# PT08M.net
KiCad netlist of a schematic drawn in EAGLE
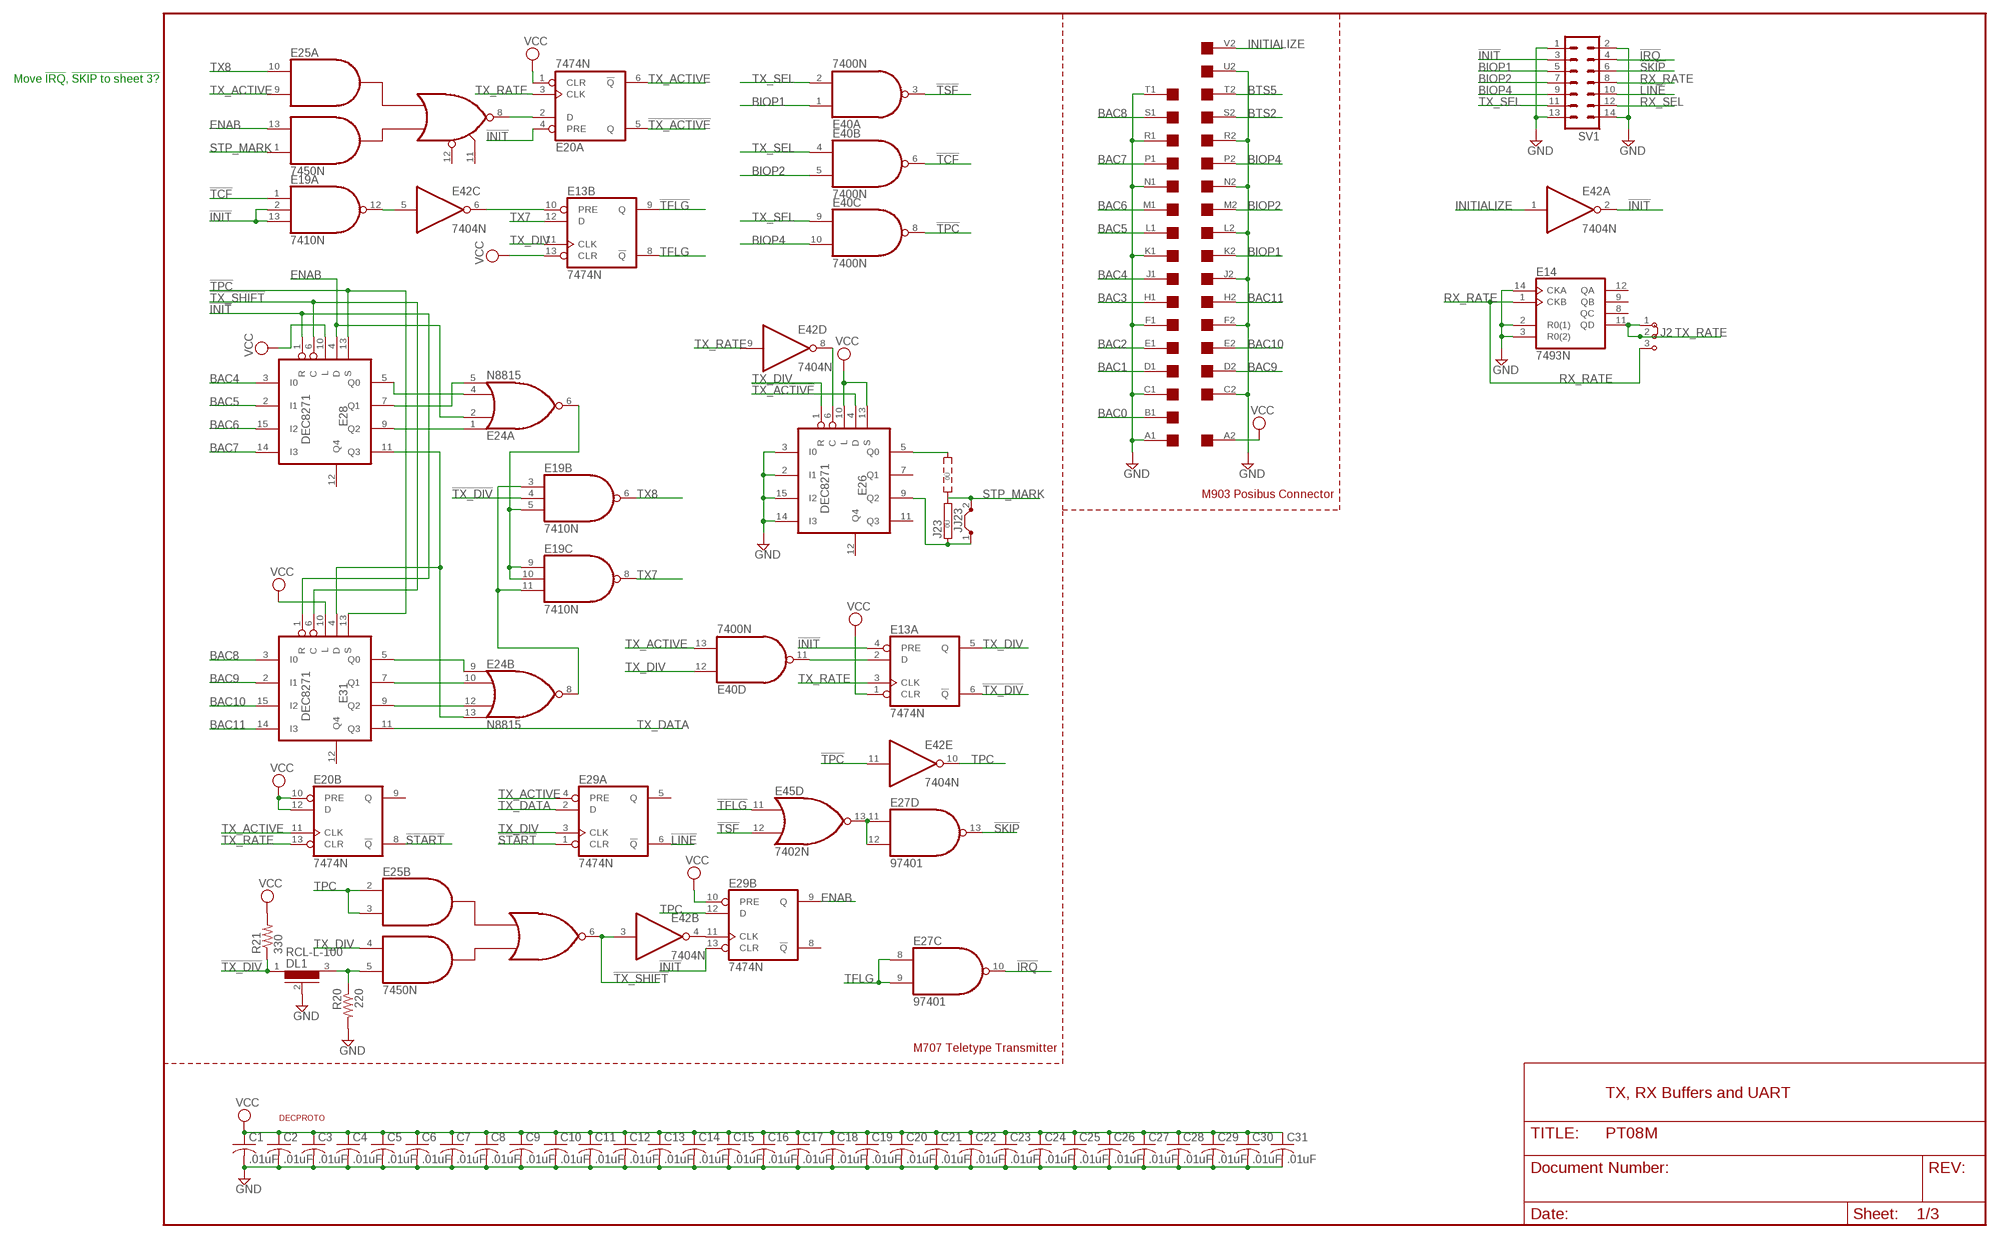
[diagram p0: schematic, sheet 1]
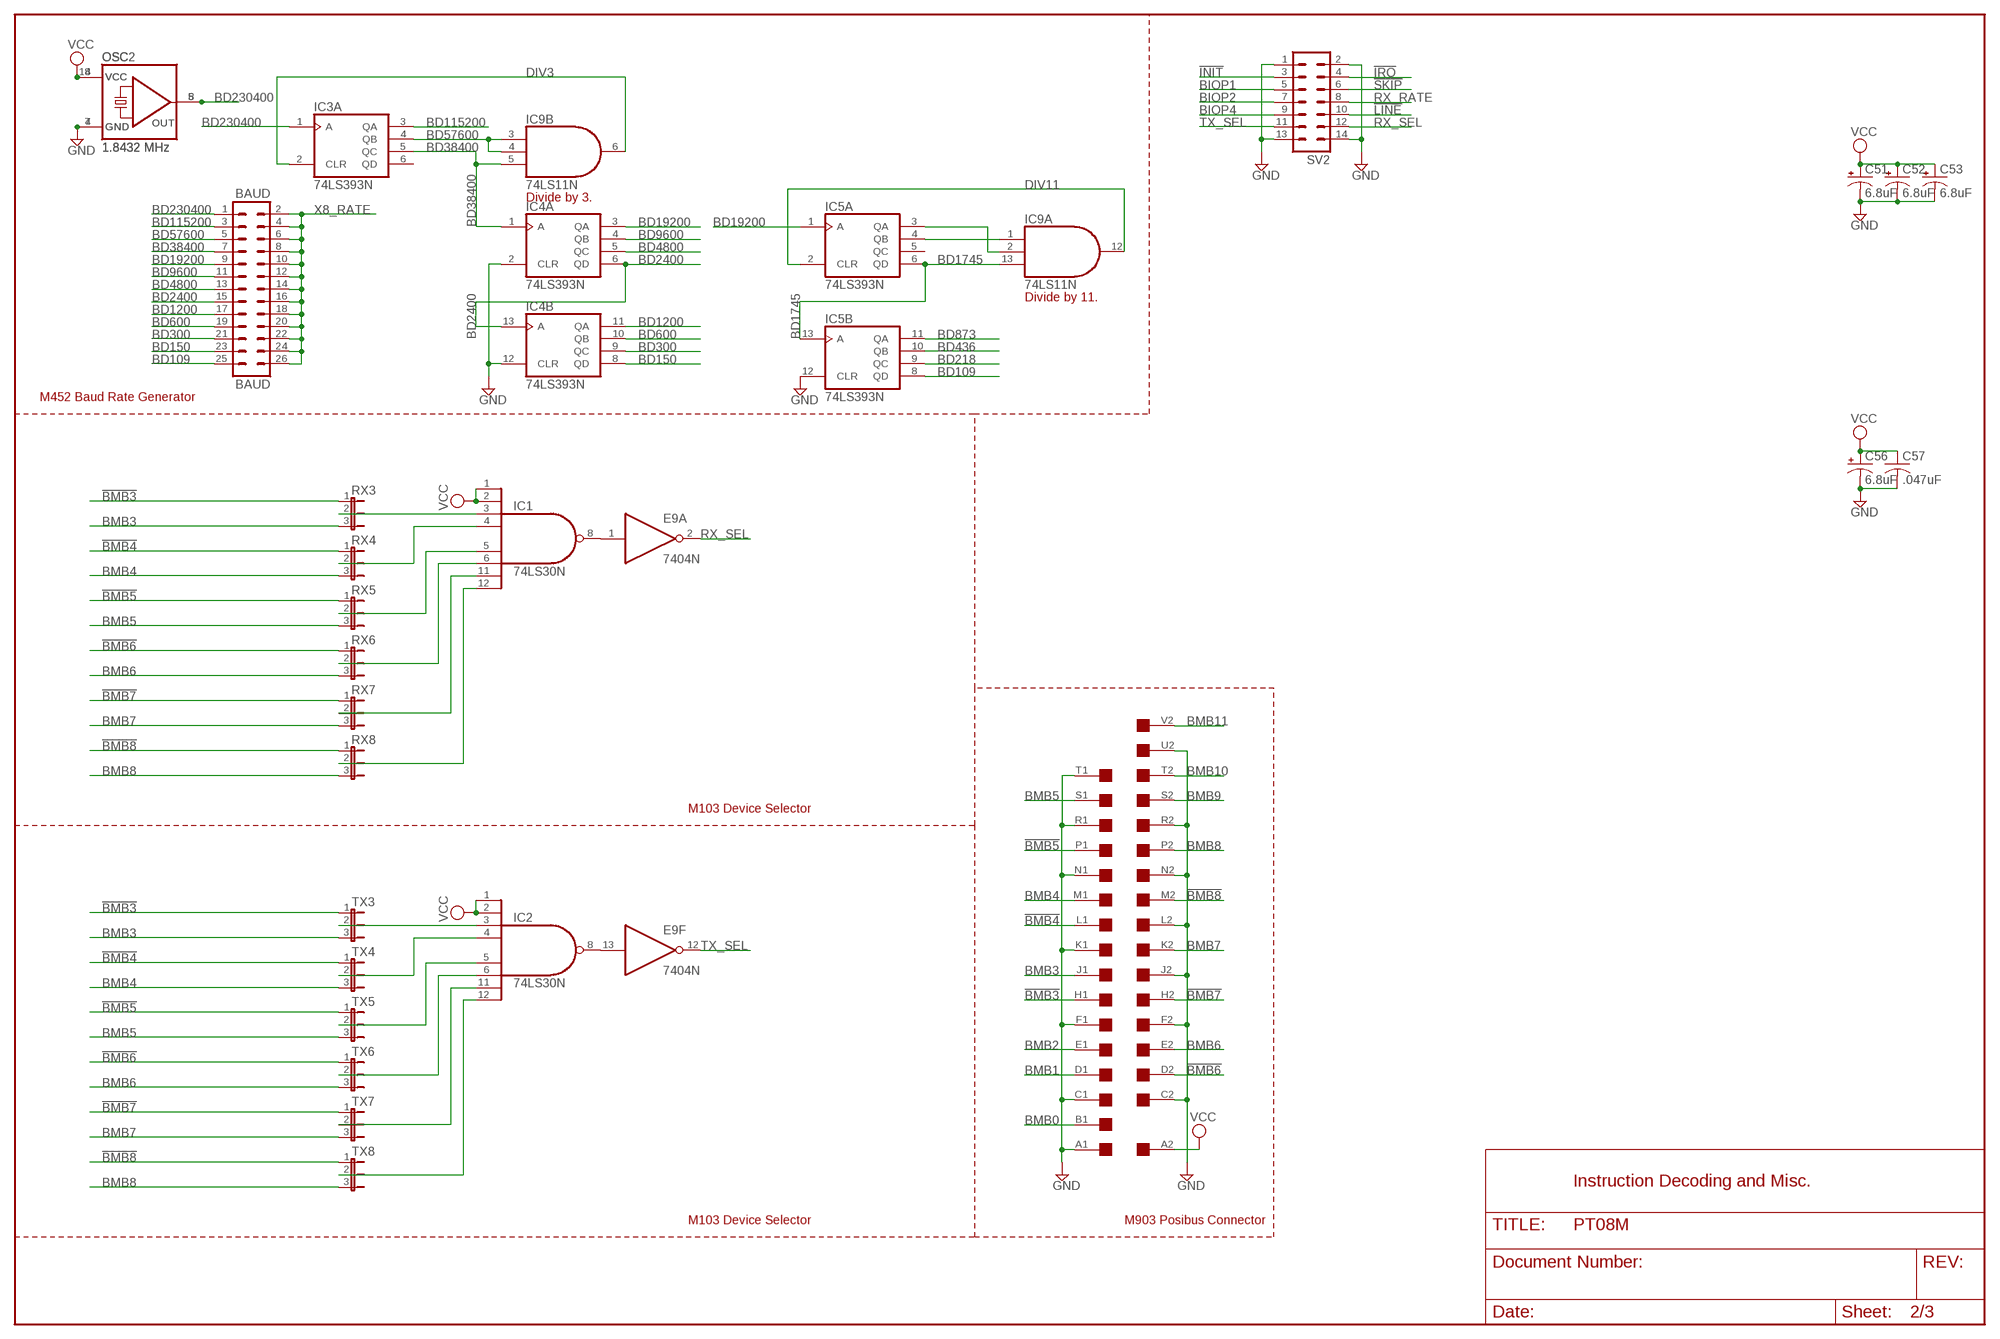
[diagram p1: schematic, sheet 2]
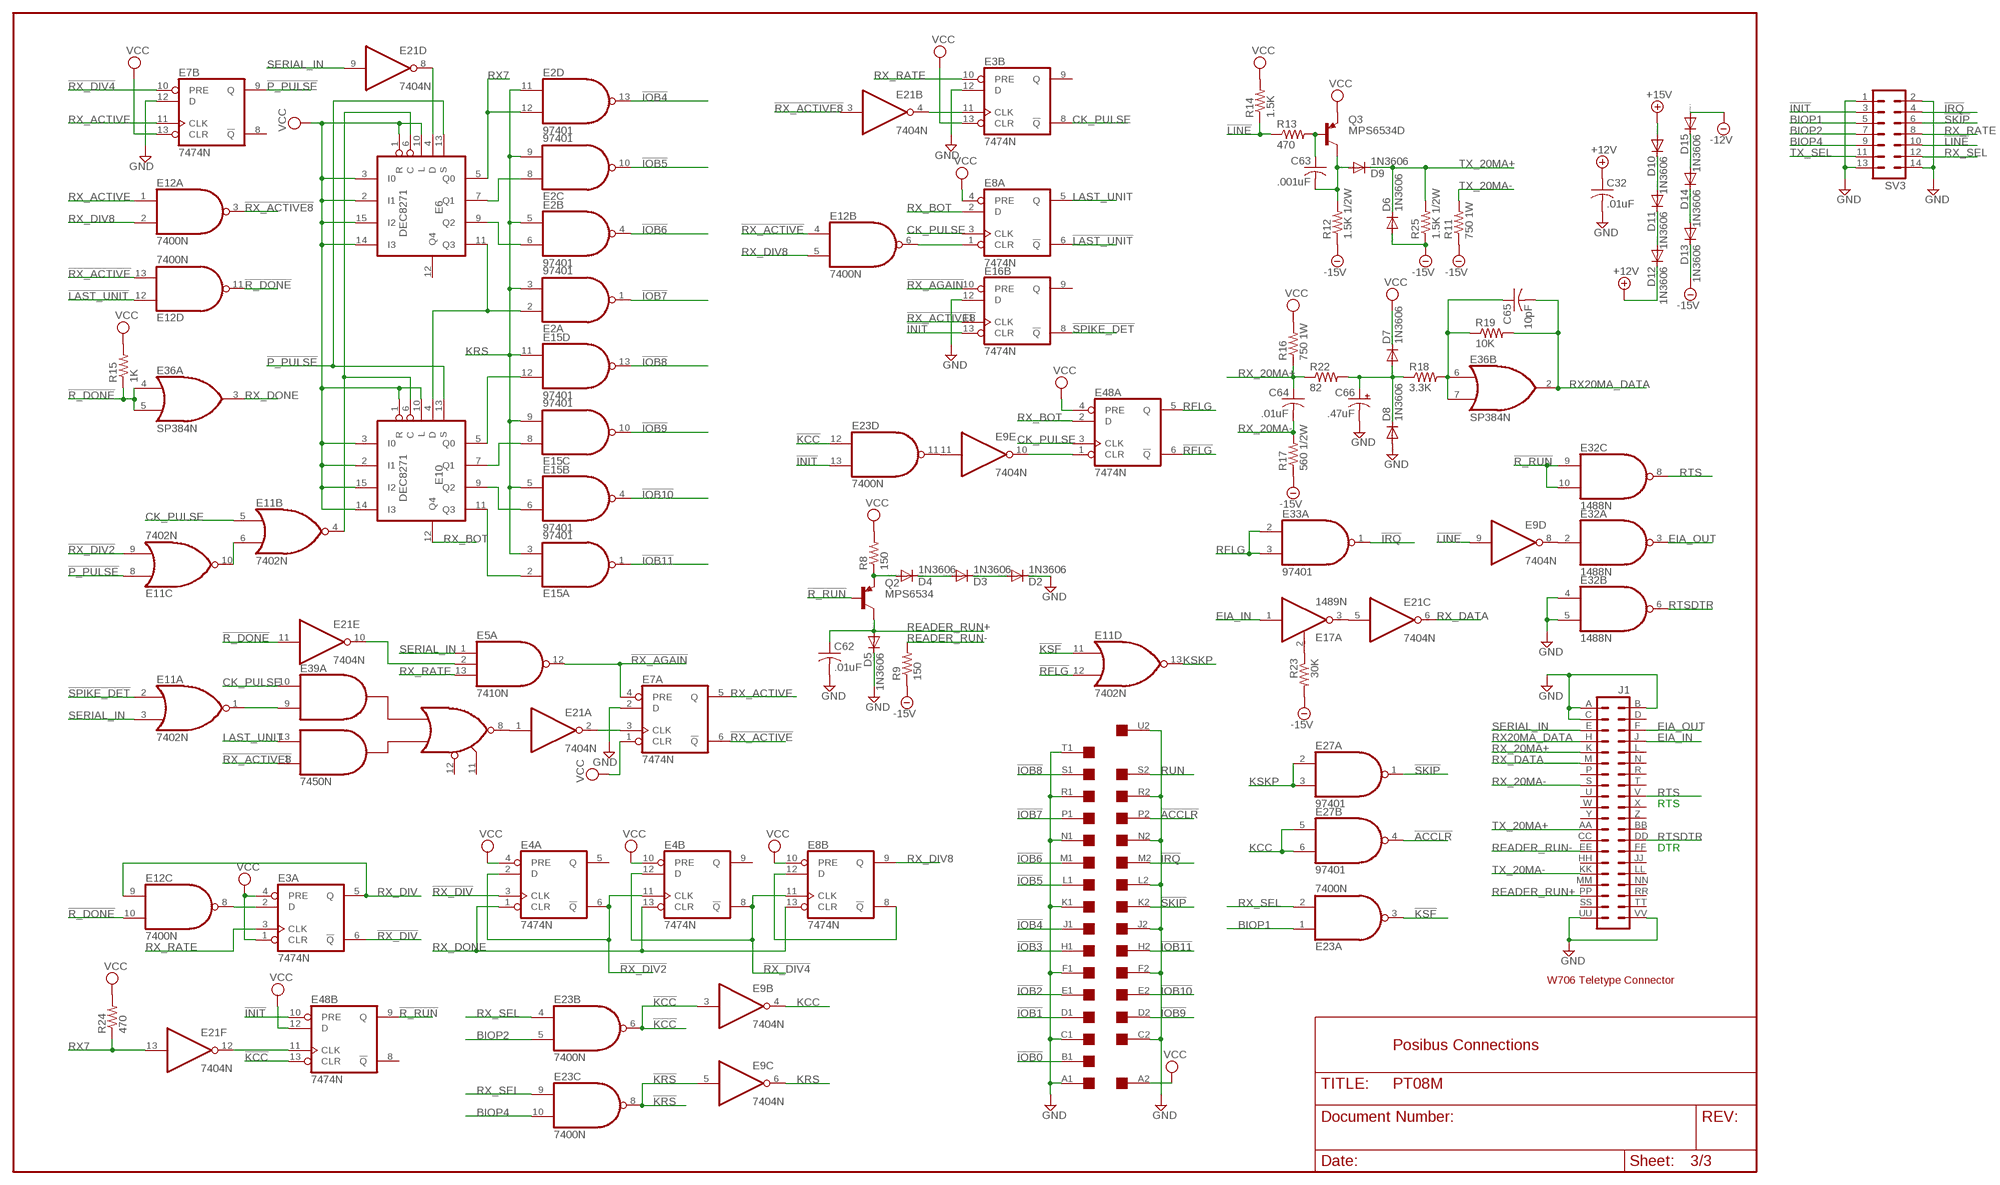
[diagram p2: schematic, sheet 3]

(export (version "E")
  (design (tool "Eeschema 10.0.6"))
  (components
    (comp (ref "C32")
      (value ".01uF")
      (footprint "eagle-import:C050-025X075")
      (libsource (lib "eagle-import") (part "C-US050-025X075"))
    )
    (comp (ref "C62")
      (value ".01uF")
      (footprint "eagle-import:C050-025X075")
      (libsource (lib "eagle-import") (part "C-US050-025X075"))
    )
    (comp (ref "C63")
      (value ".001uF")
      (footprint "eagle-import:C050-025X075")
      (libsource (lib "eagle-import") (part "C-US050-025X075"))
    )
    (comp (ref "C64")
      (value ".01uF")
      (footprint "eagle-import:C050-025X075")
      (libsource (lib "eagle-import") (part "C-US050-025X075"))
    )
    (comp (ref "C65")
      (value "10pF")
      (footprint "eagle-import:C050-025X075")
      (libsource (lib "eagle-import") (part "C-US050-025X075"))
    )
    (comp (ref "C66")
      (value ".47uF")
      (footprint "eagle-import:E15-5")
      (libsource (lib "eagle-import") (part "CPOL-USE15-5AXIAL"))
    )
    (comp (ref "D2")
      (value "1N3606")
      (footprint "eagle-import:DO35-10")
      (libsource (lib "eagle-import") (part "DIODE-DO35-10"))
    )
    (comp (ref "D3")
      (value "1N3606")
      (footprint "eagle-import:DO35-10")
      (libsource (lib "eagle-import") (part "DIODE-DO35-10"))
    )
    (comp (ref "D4")
      (value "1N3606")
      (footprint "eagle-import:DO35-10")
      (libsource (lib "eagle-import") (part "DIODE-DO35-10"))
    )
    (comp (ref "D5")
      (value "1N3606")
      (footprint "eagle-import:DO35-10")
      (libsource (lib "eagle-import") (part "DIODE-DO35-10"))
    )
    (comp (ref "D6")
      (value "1N3606")
      (footprint "eagle-import:DO35-10")
      (libsource (lib "eagle-import") (part "DIODE-DO35-10"))
    )
    (comp (ref "D7")
      (value "1N3606")
      (footprint "eagle-import:DO35-10")
      (libsource (lib "eagle-import") (part "DIODE-DO35-10"))
    )
    (comp (ref "D8")
      (value "1N3606")
      (footprint "eagle-import:DO35-10")
      (libsource (lib "eagle-import") (part "DIODE-DO35-10"))
    )
    (comp (ref "D9")
      (value "1N3606")
      (footprint "eagle-import:DO35-10")
      (libsource (lib "eagle-import") (part "DIODE-DO35-10"))
    )
    (comp (ref "D10")
      (value "1N3606")
      (footprint "eagle-import:DO35-10")
      (libsource (lib "eagle-import") (part "DIODE-DO35-10"))
    )
    (comp (ref "D11")
      (value "1N3606")
      (footprint "eagle-import:DO35-10")
      (libsource (lib "eagle-import") (part "DIODE-DO35-10"))
    )
    (comp (ref "D12")
      (value "1N3606")
      (footprint "eagle-import:DO35-10")
      (libsource (lib "eagle-import") (part "DIODE-DO35-10"))
    )
    (comp (ref "D13")
      (value "1N3606")
      (footprint "eagle-import:DO35-10")
      (libsource (lib "eagle-import") (part "DIODE-DO35-10"))
    )
    (comp (ref "D14")
      (value "1N3606")
      (footprint "eagle-import:DO35-10")
      (libsource (lib "eagle-import") (part "DIODE-DO35-10"))
    )
    (comp (ref "D15")
      (value "1N3606")
      (footprint "eagle-import:DO35-10")
      (libsource (lib "eagle-import") (part "DIODE-DO35-10"))
    )
    (comp (ref "E2")
      (value "97401")
      (footprint "eagle-import:DIL14")
      (libsource (lib "eagle-import") (part "7401NLS"))
    )
    (comp (ref "E3")
      (value "7474N")
      (footprint "eagle-import:DIL14")
      (libsource (lib "eagle-import") (part "7474NS"))
    )
    (comp (ref "E4")
      (value "7474N")
      (footprint "eagle-import:DIL14")
      (libsource (lib "eagle-import") (part "7474NS"))
    )
    (comp (ref "E5")
      (value "7410N")
      (footprint "eagle-import:DIL14")
      (libsource (lib "eagle-import") (part "7410N"))
    )
    (comp (ref "E6")
      (value "DEC8271")
      (footprint "eagle-import:DIL16")
      (libsource (lib "eagle-import") (part "DEC8271"))
    )
    (comp (ref "E7")
      (value "7474N")
      (footprint "eagle-import:DIL14")
      (libsource (lib "eagle-import") (part "7474NS"))
    )
    (comp (ref "E8")
      (value "7474N")
      (footprint "eagle-import:DIL14")
      (libsource (lib "eagle-import") (part "7474NS"))
    )
    (comp (ref "E9")
      (value "7404N")
      (footprint "eagle-import:DIL14")
      (libsource (lib "eagle-import") (part "7404N"))
    )
    (comp (ref "E10")
      (value "DEC8271")
      (footprint "eagle-import:DIL16")
      (libsource (lib "eagle-import") (part "DEC8271"))
    )
    (comp (ref "E11")
      (value "7402N")
      (footprint "eagle-import:DIL14")
      (libsource (lib "eagle-import") (part "7402N"))
    )
    (comp (ref "E12")
      (value "7400N")
      (footprint "eagle-import:DIL14")
      (libsource (lib "eagle-import") (part "7400N"))
    )
    (comp (ref "E15")
      (value "97401")
      (footprint "eagle-import:DIL14")
      (libsource (lib "eagle-import") (part "7401NLS"))
    )
    (comp (ref "E16")
      (value "7474N")
      (footprint "eagle-import:DIL14")
      (libsource (lib "eagle-import") (part "7474NS"))
    )
    (comp (ref "E17")
      (value "1489N")
      (footprint "eagle-import:DIL14")
      (libsource (lib "eagle-import") (part "1489N"))
    )
    (comp (ref "E21")
      (value "7404N")
      (footprint "eagle-import:DIL14")
      (libsource (lib "eagle-import") (part "7404N"))
    )
    (comp (ref "E23")
      (value "7400N")
      (footprint "eagle-import:DIL14")
      (libsource (lib "eagle-import") (part "7400N"))
    )
    (comp (ref "E27")
      (value "97401")
      (footprint "eagle-import:DIL14")
      (libsource (lib "eagle-import") (part "7401NLS"))
    )
    (comp (ref "E32")
      (value "1488N")
      (footprint "eagle-import:DIL14")
      (libsource (lib "eagle-import") (part "1488N"))
    )
    (comp (ref "E33")
      (value "97401")
      (footprint "eagle-import:DIL14")
      (libsource (lib "eagle-import") (part "7401NLS"))
    )
    (comp (ref "E36")
      (value "SP384N")
      (footprint "eagle-import:DIL14")
      (libsource (lib "eagle-import") (part "SP384N"))
    )
    (comp (ref "E39")
      (value "7450N")
      (footprint "eagle-import:DIL14")
      (libsource (lib "eagle-import") (part "7450N"))
    )
    (comp (ref "E48")
      (value "7474N")
      (footprint "eagle-import:DIL14")
      (libsource (lib "eagle-import") (part "7474NS"))
    )
    (comp (ref "J1")
      (value "DEC40PINH")
      (footprint "eagle-import:DEC40PINH")
      (libsource (lib "eagle-import") (part "DEC40PINH"))
    )
    (comp (ref "N16")
      (value "EDGE-2CONNECTOR")
      (footprint "eagle-import:EDGE-CON2")
      (libsource (lib "eagle-import") (part "EDGE-2CONNECTOR"))
    )
    (comp (ref "Q2")
      (value "MPS6534")
      (footprint "eagle-import:TO5")
      (libsource (lib "eagle-import") (part "-PNP-TO5"))
    )
    (comp (ref "Q3")
      (value "MPS6534D")
      (footprint "eagle-import:TO5")
      (libsource (lib "eagle-import") (part "-PNP-TO5"))
    )
    (comp (ref "R8")
      (value "150")
      (footprint "eagle-import:0207_10")
      (libsource (lib "eagle-import") (part "R-US_0207/10"))
    )
    (comp (ref "R9")
      (value "150")
      (footprint "eagle-import:0207_10")
      (libsource (lib "eagle-import") (part "R-US_0207/10"))
    )
    (comp (ref "R11")
      (value "750 1W")
      (footprint "eagle-import:0617_17")
      (libsource (lib "eagle-import") (part "R-US_0617/17"))
    )
    (comp (ref "R12")
      (value "1.5K 1/2W")
      (footprint "eagle-import:0411_15")
      (libsource (lib "eagle-import") (part "R-US_0411/15"))
    )
    (comp (ref "R13")
      (value "470")
      (footprint "eagle-import:0207_10")
      (libsource (lib "eagle-import") (part "R-US_0207/10"))
    )
    (comp (ref "R14")
      (value "1.5K")
      (footprint "eagle-import:0207_10")
      (libsource (lib "eagle-import") (part "R-US_0207/10"))
    )
    (comp (ref "R15")
      (value "1K")
      (footprint "eagle-import:0207_10")
      (libsource (lib "eagle-import") (part "R-US_0207/10"))
    )
    (comp (ref "R16")
      (value "750 1W")
      (footprint "eagle-import:0617_17")
      (libsource (lib "eagle-import") (part "R-US_0617/17"))
    )
    (comp (ref "R17")
      (value "560 1/2W")
      (footprint "eagle-import:0411_15")
      (libsource (lib "eagle-import") (part "R-US_0411/15"))
    )
    (comp (ref "R18")
      (value "3.3K")
      (footprint "eagle-import:0207_10")
      (libsource (lib "eagle-import") (part "R-US_0207/10"))
    )
    (comp (ref "R19")
      (value "10K")
      (footprint "eagle-import:0207_10")
      (libsource (lib "eagle-import") (part "R-US_0207/10"))
    )
    (comp (ref "R22")
      (value "82")
      (footprint "eagle-import:0207_10")
      (libsource (lib "eagle-import") (part "R-US_0207/10"))
    )
    (comp (ref "R23")
      (value "30K")
      (footprint "eagle-import:0207_10")
      (libsource (lib "eagle-import") (part "R-US_0207/10"))
    )
    (comp (ref "R24")
      (value "470")
      (footprint "eagle-import:0207_10")
      (libsource (lib "eagle-import") (part "R-US_0207/10"))
    )
    (comp (ref "R25")
      (value "1.5K 1/2W")
      (footprint "eagle-import:0411_15")
      (libsource (lib "eagle-import") (part "R-US_0411/15"))
    )
    (comp (ref "SV3")
      (value "ML14L")
      (footprint "eagle-import:ML14L")
      (libsource (lib "eagle-import") (part "ML14L"))
    )
    (comp (ref "BAUD")
      (value "BAUD")
      (footprint "eagle-import:MA13-2")
      (libsource (lib "eagle-import") (part "MA13-2"))
    )
    (comp (ref "C51")
      (value "6.8uF")
      (footprint "eagle-import:E12-8")
      (libsource (lib "eagle-import") (part "CPOL-USE20-8AXIAL"))
    )
    (comp (ref "C52")
      (value "6.8uF")
      (footprint "eagle-import:E12-8")
      (libsource (lib "eagle-import") (part "CPOL-USE20-8AXIAL"))
    )
    (comp (ref "C53")
      (value "6.8uF")
      (footprint "eagle-import:E12-8")
      (libsource (lib "eagle-import") (part "CPOL-USE20-8AXIAL"))
    )
    (comp (ref "C56")
      (value "6.8uF")
      (footprint "eagle-import:E12-8")
      (libsource (lib "eagle-import") (part "CPOL-USE20-8AXIAL"))
    )
    (comp (ref "C57")
      (value ".047uF")
      (footprint "eagle-import:C050-025X075")
      (libsource (lib "eagle-import") (part "C-US050-025X075"))
    )
    (comp (ref "IC1")
      (value "74LS30N")
      (footprint "eagle-import:DIL14")
      (libsource (lib "eagle-import") (part "7430NLS"))
    )
    (comp (ref "IC2")
      (value "74LS30N")
      (footprint "eagle-import:DIL14")
      (libsource (lib "eagle-import") (part "7430NLS"))
    )
    (comp (ref "IC3")
      (value "74LS393N")
      (footprint "eagle-import:DIL14")
      (libsource (lib "eagle-import") (part "74393NLS"))
    )
    (comp (ref "IC4")
      (value "74LS393N")
      (footprint "eagle-import:DIL14")
      (libsource (lib "eagle-import") (part "74393NLS"))
    )
    (comp (ref "IC5")
      (value "74LS393N")
      (footprint "eagle-import:DIL14")
      (libsource (lib "eagle-import") (part "74393NLS"))
    )
    (comp (ref "IC9")
      (value "74LS11N")
      (footprint "eagle-import:DIL14")
      (libsource (lib "eagle-import") (part "7411NLS"))
    )
    (comp (ref "N15")
      (value "EDGE-2CONNECTOR")
      (footprint "eagle-import:EDGE-CON2")
      (libsource (lib "eagle-import") (part "EDGE-2CONNECTOR"))
    )
    (comp (ref "OSC")
      (value "1.8432 MHz")
      (footprint "eagle-import:DIL08S")
      (libsource (lib "eagle-import") (part "QG5460"))
    )
    (comp (ref "OSC2")
      (value "1.8432 MHz")
      (footprint "eagle-import:DIL14S")
      (libsource (lib "eagle-import") (part "QG5860"))
    )
    (comp (ref "RX3")
      (value "JP2E")
      (footprint "eagle-import:JP2")
      (libsource (lib "eagle-import") (part "JP2E"))
    )
    (comp (ref "RX4")
      (value "JP2E")
      (footprint "eagle-import:JP2")
      (libsource (lib "eagle-import") (part "JP2E"))
    )
    (comp (ref "RX5")
      (value "JP2E")
      (footprint "eagle-import:JP2")
      (libsource (lib "eagle-import") (part "JP2E"))
    )
    (comp (ref "RX6")
      (value "JP2E")
      (footprint "eagle-import:JP2")
      (libsource (lib "eagle-import") (part "JP2E"))
    )
    (comp (ref "RX7")
      (value "JP2E")
      (footprint "eagle-import:JP2")
      (libsource (lib "eagle-import") (part "JP2E"))
    )
    (comp (ref "RX8")
      (value "JP2E")
      (footprint "eagle-import:JP2")
      (libsource (lib "eagle-import") (part "JP2E"))
    )
    (comp (ref "SV2")
      (value "ML14L")
      (footprint "eagle-import:ML14L")
      (libsource (lib "eagle-import") (part "ML14L"))
    )
    (comp (ref "TX3")
      (value "JP2E")
      (footprint "eagle-import:JP2")
      (libsource (lib "eagle-import") (part "JP2E"))
    )
    (comp (ref "TX4")
      (value "JP2E")
      (footprint "eagle-import:JP2")
      (libsource (lib "eagle-import") (part "JP2E"))
    )
    (comp (ref "TX5")
      (value "JP2E")
      (footprint "eagle-import:JP2")
      (libsource (lib "eagle-import") (part "JP2E"))
    )
    (comp (ref "TX6")
      (value "JP2E")
      (footprint "eagle-import:JP2")
      (libsource (lib "eagle-import") (part "JP2E"))
    )
    (comp (ref "TX7")
      (value "JP2E")
      (footprint "eagle-import:JP2")
      (libsource (lib "eagle-import") (part "JP2E"))
    )
    (comp (ref "TX8")
      (value "JP2E")
      (footprint "eagle-import:JP2")
      (libsource (lib "eagle-import") (part "JP2E"))
    )
    (comp (ref "C1")
      (value ".01uF")
      (footprint "eagle-import:C050-025X075")
      (libsource (lib "eagle-import") (part "C-US050-025X075"))
    )
    (comp (ref "C2")
      (value ".01uF")
      (footprint "eagle-import:C050-025X075")
      (libsource (lib "eagle-import") (part "C-US050-025X075"))
    )
    (comp (ref "C3")
      (value ".01uF")
      (footprint "eagle-import:C050-025X075")
      (libsource (lib "eagle-import") (part "C-US050-025X075"))
    )
    (comp (ref "C4")
      (value ".01uF")
      (footprint "eagle-import:C050-025X075")
      (libsource (lib "eagle-import") (part "C-US050-025X075"))
    )
    (comp (ref "C5")
      (value ".01uF")
      (footprint "eagle-import:C050-025X075")
      (libsource (lib "eagle-import") (part "C-US050-025X075"))
    )
    (comp (ref "C6")
      (value ".01uF")
      (footprint "eagle-import:C050-025X075")
      (libsource (lib "eagle-import") (part "C-US050-025X075"))
    )
    (comp (ref "C7")
      (value ".01uF")
      (footprint "eagle-import:C050-025X075")
      (libsource (lib "eagle-import") (part "C-US050-025X075"))
    )
    (comp (ref "C8")
      (value ".01uF")
      (footprint "eagle-import:C050-025X075")
      (libsource (lib "eagle-import") (part "C-US050-025X075"))
    )
    (comp (ref "C9")
      (value ".01uF")
      (footprint "eagle-import:C050-025X075")
      (libsource (lib "eagle-import") (part "C-US050-025X075"))
    )
    (comp (ref "C10")
      (value ".01uF")
      (footprint "eagle-import:C050-025X075")
      (libsource (lib "eagle-import") (part "C-US050-025X075"))
    )
    (comp (ref "C11")
      (value ".01uF")
      (footprint "eagle-import:C050-025X075")
      (libsource (lib "eagle-import") (part "C-US050-025X075"))
    )
    (comp (ref "C12")
      (value ".01uF")
      (footprint "eagle-import:C050-025X075")
      (libsource (lib "eagle-import") (part "C-US050-025X075"))
    )
    (comp (ref "C13")
      (value ".01uF")
      (footprint "eagle-import:C050-025X075")
      (libsource (lib "eagle-import") (part "C-US050-025X075"))
    )
    (comp (ref "C14")
      (value ".01uF")
      (footprint "eagle-import:C050-025X075")
      (libsource (lib "eagle-import") (part "C-US050-025X075"))
    )
    (comp (ref "C15")
      (value ".01uF")
      (footprint "eagle-import:C050-025X075")
      (libsource (lib "eagle-import") (part "C-US050-025X075"))
    )
    (comp (ref "C16")
      (value ".01uF")
      (footprint "eagle-import:C050-025X075")
      (libsource (lib "eagle-import") (part "C-US050-025X075"))
    )
    (comp (ref "C17")
      (value ".01uF")
      (footprint "eagle-import:C050-025X075")
      (libsource (lib "eagle-import") (part "C-US050-025X075"))
    )
    (comp (ref "C18")
      (value ".01uF")
      (footprint "eagle-import:C050-025X075")
      (libsource (lib "eagle-import") (part "C-US050-025X075"))
    )
    (comp (ref "C19")
      (value ".01uF")
      (footprint "eagle-import:C050-025X075")
      (libsource (lib "eagle-import") (part "C-US050-025X075"))
    )
    (comp (ref "C20")
      (value ".01uF")
      (footprint "eagle-import:C050-025X075")
      (libsource (lib "eagle-import") (part "C-US050-025X075"))
    )
    (comp (ref "C21")
      (value ".01uF")
      (footprint "eagle-import:C050-025X075")
      (libsource (lib "eagle-import") (part "C-US050-025X075"))
    )
    (comp (ref "C22")
      (value ".01uF")
      (footprint "eagle-import:C050-025X075")
      (libsource (lib "eagle-import") (part "C-US050-025X075"))
    )
    (comp (ref "C23")
      (value ".01uF")
      (footprint "eagle-import:C050-025X075")
      (libsource (lib "eagle-import") (part "C-US050-025X075"))
    )
    (comp (ref "C24")
      (value ".01uF")
      (footprint "eagle-import:C050-025X075")
      (libsource (lib "eagle-import") (part "C-US050-025X075"))
    )
    (comp (ref "C25")
      (value ".01uF")
      (footprint "eagle-import:C050-025X075")
      (libsource (lib "eagle-import") (part "C-US050-025X075"))
    )
    (comp (ref "C26")
      (value ".01uF")
      (footprint "eagle-import:C050-025X075")
      (libsource (lib "eagle-import") (part "C-US050-025X075"))
    )
    (comp (ref "C27")
      (value ".01uF")
      (footprint "eagle-import:C050-025X075")
      (libsource (lib "eagle-import") (part "C-US050-025X075"))
    )
    (comp (ref "C28")
      (value ".01uF")
      (footprint "eagle-import:C050-025X075")
      (libsource (lib "eagle-import") (part "C-US050-025X075"))
    )
    (comp (ref "C29")
      (value ".01uF")
      (footprint "eagle-import:C050-025X075")
      (libsource (lib "eagle-import") (part "C-US050-025X075"))
    )
    (comp (ref "C30")
      (value ".01uF")
      (footprint "eagle-import:C050-025X075")
      (libsource (lib "eagle-import") (part "C-US050-025X075"))
    )
    (comp (ref "C31")
      (value ".01uF")
      (footprint "eagle-import:C050-025X075")
      (libsource (lib "eagle-import") (part "C-US050-025X075"))
    )
    (comp (ref "DL1")
      (value "RCL-L-100")
      (footprint "eagle-import:RCL-L-00-05")
      (libsource (lib "eagle-import") (part "RCL-L-00-05"))
    )
    (comp (ref "E13")
      (value "7474N")
      (footprint "eagle-import:DIL14")
      (libsource (lib "eagle-import") (part "7474NS"))
    )
    (comp (ref "E14")
      (value "7493N")
      (footprint "eagle-import:DIL14")
      (libsource (lib "eagle-import") (part "7493NLS"))
    )
    (comp (ref "E19")
      (value "7410N")
      (footprint "eagle-import:DIL14")
      (libsource (lib "eagle-import") (part "7410N"))
    )
    (comp (ref "E20")
      (value "7474N")
      (footprint "eagle-import:DIL14")
      (libsource (lib "eagle-import") (part "7474NS"))
    )
    (comp (ref "E24")
      (value "N8815")
      (footprint "eagle-import:DIL14")
      (libsource (lib "eagle-import") (part "N8815"))
    )
    (comp (ref "E25")
      (value "7450N")
      (footprint "eagle-import:DIL14")
      (libsource (lib "eagle-import") (part "7450N"))
    )
    (comp (ref "E26")
      (value "DEC8271")
      (footprint "eagle-import:DIL16")
      (libsource (lib "eagle-import") (part "DEC8271"))
    )
    (comp (ref "E28")
      (value "DEC8271")
      (footprint "eagle-import:DIL16")
      (libsource (lib "eagle-import") (part "DEC8271"))
    )
    (comp (ref "E29")
      (value "7474N")
      (footprint "eagle-import:DIL14")
      (libsource (lib "eagle-import") (part "7474NS"))
    )
    (comp (ref "E31")
      (value "DEC8271")
      (footprint "eagle-import:DIL16")
      (libsource (lib "eagle-import") (part "DEC8271"))
    )
    (comp (ref "E40")
      (value "7400N")
      (footprint "eagle-import:DIL14")
      (libsource (lib "eagle-import") (part "7400N"))
    )
    (comp (ref "E42")
      (value "7404N")
      (footprint "eagle-import:DIL14")
      (libsource (lib "eagle-import") (part "7404N"))
    )
    (comp (ref "E45")
      (value "7402N")
      (footprint "eagle-import:DIL14")
      (libsource (lib "eagle-import") (part "7402N"))
    )
    (comp (ref "J2")
      (value "J2X2MM")
      (footprint "eagle-import:04C")
      (libsource (lib "eagle-import") (part "J2X2MM"))
    )
    (comp (ref "J23")
      (value "0R2")
      (footprint "eagle-import:0R2_10")
      (libsource (lib "eagle-import") (part "0R2"))
    )
    (comp (ref "JJ23")
      (value "J10MM")
      (footprint "eagle-import:10")
      (libsource (lib "eagle-import") (part "J10MM"))
    )
    (comp (ref "N14")
      (value "EDGE-2CONNECTOR")
      (footprint "eagle-import:EDGE-CON2")
      (libsource (lib "eagle-import") (part "EDGE-2CONNECTOR"))
    )
    (comp (ref "R20")
      (value "220")
      (footprint "eagle-import:0207_10")
      (libsource (lib "eagle-import") (part "R-US_0207/10"))
    )
    (comp (ref "R21")
      (value "330")
      (footprint "eagle-import:0207_10")
      (libsource (lib "eagle-import") (part "R-US_0207/10"))
    )
    (comp (ref "SV1")
      (value "ML14L")
      (footprint "eagle-import:ML14L")
      (libsource (lib "eagle-import") (part "ML14L"))
    )
    (comp (ref "U$2")
      (value "DECPROTO")
      (footprint "eagle-import:DECPROTO111")
      (libsource (lib "eagle-import") (part "DECPROTO"))
    )
  )
  (nets
    (net (code "1") (name "+12V") (class "Default")
      (node (ref "C32") (pin "1") (pinfunction "1_1") (pintype "passive"))
      (node (ref "D12") (pin "C") (pinfunction "C_C") (pintype "passive"))
    )
    (net (code "2") (name "+15V") (class "Default")
      (node (ref "D10") (pin "A") (pinfunction "A_A") (pintype "passive"))
    )
    (net (code "3") (name "-12V") (class "Default")
      (node (ref "D15") (pin "A") (pinfunction "A_A") (pintype "passive"))
    )
    (net (code "4") (name "-15V") (class "Default")
      (node (ref "D13") (pin "C") (pinfunction "C_C") (pintype "passive"))
      (node (ref "D6") (pin "A") (pinfunction "A_A") (pintype "passive"))
      (node (ref "R11") (pin "1") (pinfunction "1_1") (pintype "passive"))
      (node (ref "R12") (pin "1") (pinfunction "1_1") (pintype "passive"))
      (node (ref "R17") (pin "1") (pinfunction "1_1") (pintype "passive"))
      (node (ref "R23") (pin "2") (pinfunction "2_2") (pintype "passive"))
      (node (ref "R25") (pin "1") (pinfunction "1_1") (pintype "passive"))
      (node (ref "R9") (pin "1") (pinfunction "1_1") (pintype "passive"))
    )
    (net (code "5") (name "BAC0") (class "Default")
      (node (ref "N14") (pin "B1") (pinfunction "1_B1") (pintype "bidirectional"))
    )
    (net (code "6") (name "BAC1") (class "Default")
      (node (ref "N14") (pin "D1") (pinfunction "1_D1") (pintype "bidirectional"))
    )
    (net (code "7") (name "BAC2") (class "Default")
      (node (ref "N14") (pin "E1") (pinfunction "1_E1") (pintype "bidirectional"))
    )
    (net (code "8") (name "BAC3") (class "Default")
      (node (ref "N14") (pin "H1") (pinfunction "1_H1") (pintype "bidirectional"))
    )
    (net (code "9") (name "BAC4") (class "Default")
      (node (ref "E28") (pin "3") (pinfunction "I0_3") (pintype "input"))
      (node (ref "N14") (pin "J1") (pinfunction "1_J1") (pintype "bidirectional"))
    )
    (net (code "10") (name "BAC5") (class "Default")
      (node (ref "E28") (pin "2") (pinfunction "I1_2") (pintype "input"))
      (node (ref "N14") (pin "L1") (pinfunction "1_L1") (pintype "bidirectional"))
    )
    (net (code "11") (name "BAC6") (class "Default")
      (node (ref "E28") (pin "15") (pinfunction "I2_15") (pintype "input"))
      (node (ref "N14") (pin "M1") (pinfunction "1_M1") (pintype "bidirectional"))
    )
    (net (code "12") (name "BAC7") (class "Default")
      (node (ref "E28") (pin "14") (pinfunction "I3_14") (pintype "input"))
      (node (ref "N14") (pin "P1") (pinfunction "1_P1") (pintype "bidirectional"))
    )
    (net (code "13") (name "BAC8") (class "Default")
      (node (ref "E31") (pin "3") (pinfunction "I0_3") (pintype "input"))
      (node (ref "N14") (pin "S1") (pinfunction "1_S1") (pintype "bidirectional"))
    )
    (net (code "14") (name "BAC9") (class "Default")
      (node (ref "E31") (pin "2") (pinfunction "I1_2") (pintype "input"))
      (node (ref "N14") (pin "D2") (pinfunction "1_D2") (pintype "bidirectional"))
    )
    (net (code "15") (name "BAC10") (class "Default")
      (node (ref "E31") (pin "15") (pinfunction "I2_15") (pintype "input"))
      (node (ref "N14") (pin "E2") (pinfunction "1_E2") (pintype "bidirectional"))
    )
    (net (code "16") (name "BAC11") (class "Default")
      (node (ref "E31") (pin "14") (pinfunction "I3_14") (pintype "input"))
      (node (ref "N14") (pin "H2") (pinfunction "1_H2") (pintype "bidirectional"))
    )
    (net (code "17") (name "BD109") (class "Default")
      (node (ref "BAUD") (pin "25") (pinfunction "25_25") (pintype "passive"))
      (node (ref "IC5") (pin "8") (pinfunction "QD_8") (pintype "output"))
    )
    (net (code "18") (name "BD150") (class "Default")
      (node (ref "BAUD") (pin "23") (pinfunction "23_23") (pintype "passive"))
      (node (ref "IC4") (pin "8") (pinfunction "QD_8") (pintype "output"))
    )
    (net (code "19") (name "BD218") (class "Default")
      (node (ref "IC5") (pin "9") (pinfunction "QC_9") (pintype "output"))
    )
    (net (code "20") (name "BD300") (class "Default")
      (node (ref "BAUD") (pin "21") (pinfunction "21_21") (pintype "passive"))
      (node (ref "IC4") (pin "9") (pinfunction "QC_9") (pintype "output"))
    )
    (net (code "21") (name "BD436") (class "Default")
      (node (ref "IC5") (pin "10") (pinfunction "QB_10") (pintype "output"))
    )
    (net (code "22") (name "BD600") (class "Default")
      (node (ref "BAUD") (pin "19") (pinfunction "19_19") (pintype "passive"))
      (node (ref "IC4") (pin "10") (pinfunction "QB_10") (pintype "output"))
    )
    (net (code "23") (name "BD873") (class "Default")
      (node (ref "IC5") (pin "11") (pinfunction "QA_11") (pintype "output"))
    )
    (net (code "24") (name "BD1200") (class "Default")
      (node (ref "BAUD") (pin "17") (pinfunction "17_17") (pintype "passive"))
      (node (ref "IC4") (pin "11") (pinfunction "QA_11") (pintype "output"))
    )
    (net (code "25") (name "BD1745") (class "Default")
      (node (ref "IC5") (pin "13") (pinfunction "A_13") (pintype "input"))
      (node (ref "IC5") (pin "6") (pinfunction "QD_6") (pintype "output"))
      (node (ref "IC9") (pin "13") (pinfunction "I2_13") (pintype "input"))
    )
    (net (code "26") (name "BD2400") (class "Default")
      (node (ref "BAUD") (pin "15") (pinfunction "15_15") (pintype "passive"))
      (node (ref "IC4") (pin "13") (pinfunction "A_13") (pintype "input"))
      (node (ref "IC4") (pin "6") (pinfunction "QD_6") (pintype "output"))
    )
    (net (code "27") (name "BD4800") (class "Default")
      (node (ref "BAUD") (pin "13") (pinfunction "13_13") (pintype "passive"))
      (node (ref "IC4") (pin "5") (pinfunction "QC_5") (pintype "output"))
    )
    (net (code "28") (name "BD9600") (class "Default")
      (node (ref "BAUD") (pin "11") (pinfunction "11_11") (pintype "passive"))
      (node (ref "IC4") (pin "4") (pinfunction "QB_4") (pintype "output"))
    )
    (net (code "29") (name "BD19200") (class "Default")
      (node (ref "BAUD") (pin "9") (pinfunction "9_9") (pintype "passive"))
      (node (ref "IC4") (pin "3") (pinfunction "QA_3") (pintype "output"))
      (node (ref "IC5") (pin "1") (pinfunction "A_1") (pintype "input"))
    )
    (net (code "30") (name "BD38400") (class "Default")
      (node (ref "BAUD") (pin "7") (pinfunction "7_7") (pintype "passive"))
      (node (ref "IC3") (pin "5") (pinfunction "QC_5") (pintype "output"))
      (node (ref "IC4") (pin "1") (pinfunction "A_1") (pintype "input"))
      (node (ref "IC9") (pin "5") (pinfunction "I2_5") (pintype "input"))
    )
    (net (code "31") (name "BD57600") (class "Default")
      (node (ref "BAUD") (pin "5") (pinfunction "5_5") (pintype "passive"))
      (node (ref "IC3") (pin "4") (pinfunction "QB_4") (pintype "output"))
      (node (ref "IC9") (pin "3") (pinfunction "I0_3") (pintype "input"))
      (node (ref "IC9") (pin "4") (pinfunction "I1_4") (pintype "input"))
    )
    (net (code "32") (name "BD115200") (class "Default")
      (node (ref "BAUD") (pin "3") (pinfunction "3_3") (pintype "passive"))
      (node (ref "IC3") (pin "3") (pinfunction "QA_3") (pintype "output"))
    )
    (net (code "33") (name "BD230400") (class "Default")
      (node (ref "BAUD") (pin "1") (pinfunction "1_1") (pintype "passive"))
      (node (ref "IC3") (pin "1") (pinfunction "A_1") (pintype "input"))
      (node (ref "OSC") (pin "5") (pinfunction "OUT_5") (pintype "output"))
      (node (ref "OSC2") (pin "8") (pinfunction "OUT_8") (pintype "output"))
    )
    (net (code "34") (name "BIOP1") (class "Default")
      (node (ref "E23") (pin "1") (pinfunction "I0_1") (pintype "input"))
      (node (ref "E40") (pin "1") (pinfunction "I0_1") (pintype "input"))
      (node (ref "N14") (pin "K2") (pinfunction "1_K2") (pintype "bidirectional"))
      (node (ref "SV1") (pin "5") (pinfunction "5_5") (pintype "passive"))
      (node (ref "SV2") (pin "5") (pinfunction "5_5") (pintype "passive"))
      (node (ref "SV3") (pin "5") (pinfunction "5_5") (pintype "passive"))
    )
    (net (code "35") (name "BIOP2") (class "Default")
      (node (ref "E23") (pin "5") (pinfunction "I1_5") (pintype "input"))
      (node (ref "E40") (pin "5") (pinfunction "I1_5") (pintype "input"))
      (node (ref "N14") (pin "M2") (pinfunction "1_M2") (pintype "bidirectional"))
      (node (ref "SV1") (pin "7") (pinfunction "7_7") (pintype "passive"))
      (node (ref "SV2") (pin "7") (pinfunction "7_7") (pintype "passive"))
      (node (ref "SV3") (pin "7") (pinfunction "7_7") (pintype "passive"))
    )
    (net (code "36") (name "BIOP4") (class "Default")
      (node (ref "E23") (pin "10") (pinfunction "I1_10") (pintype "input"))
      (node (ref "E40") (pin "10") (pinfunction "I1_10") (pintype "input"))
      (node (ref "N14") (pin "P2") (pinfunction "1_P2") (pintype "bidirectional"))
      (node (ref "SV1") (pin "9") (pinfunction "9_9") (pintype "passive"))
      (node (ref "SV2") (pin "9") (pinfunction "9_9") (pintype "passive"))
      (node (ref "SV3") (pin "9") (pinfunction "9_9") (pintype "passive"))
    )
    (net (code "37") (name "BMB0") (class "Default")
      (node (ref "N15") (pin "B1") (pinfunction "1_B1") (pintype "bidirectional"))
    )
    (net (code "38") (name "BMB1") (class "Default")
      (node (ref "N15") (pin "D1") (pinfunction "1_D1") (pintype "bidirectional"))
    )
    (net (code "39") (name "BMB2") (class "Default")
      (node (ref "N15") (pin "E1") (pinfunction "1_E1") (pintype "bidirectional"))
    )
    (net (code "40") (name "BMB3") (class "Default")
      (node (ref "N15") (pin "J1") (pinfunction "1_J1") (pintype "bidirectional"))
      (node (ref "RX3") (pin "3") (pinfunction "3_3") (pintype "passive"))
      (node (ref "TX3") (pin "3") (pinfunction "3_3") (pintype "passive"))
    )
    (net (code "41") (name "BMB4") (class "Default")
      (node (ref "N15") (pin "M1") (pinfunction "1_M1") (pintype "bidirectional"))
      (node (ref "RX4") (pin "3") (pinfunction "3_3") (pintype "passive"))
      (node (ref "TX4") (pin "3") (pinfunction "3_3") (pintype "passive"))
    )
    (net (code "42") (name "BMB5") (class "Default")
      (node (ref "N15") (pin "S1") (pinfunction "1_S1") (pintype "bidirectional"))
      (node (ref "RX5") (pin "3") (pinfunction "3_3") (pintype "passive"))
      (node (ref "TX5") (pin "3") (pinfunction "3_3") (pintype "passive"))
    )
    (net (code "43") (name "BMB6") (class "Default")
      (node (ref "N15") (pin "E2") (pinfunction "1_E2") (pintype "bidirectional"))
      (node (ref "RX6") (pin "3") (pinfunction "3_3") (pintype "passive"))
      (node (ref "TX6") (pin "3") (pinfunction "3_3") (pintype "passive"))
    )
    (net (code "44") (name "BMB7") (class "Default")
      (node (ref "N15") (pin "K2") (pinfunction "1_K2") (pintype "bidirectional"))
      (node (ref "RX7") (pin "3") (pinfunction "3_3") (pintype "passive"))
      (node (ref "TX7") (pin "3") (pinfunction "3_3") (pintype "passive"))
    )
    (net (code "45") (name "BMB8") (class "Default")
      (node (ref "N15") (pin "P2") (pinfunction "1_P2") (pintype "bidirectional"))
      (node (ref "RX8") (pin "3") (pinfunction "3_3") (pintype "passive"))
      (node (ref "TX8") (pin "3") (pinfunction "3_3") (pintype "passive"))
    )
    (net (code "46") (name "BMB9") (class "Default")
      (node (ref "N15") (pin "S2") (pinfunction "1_S2") (pintype "bidirectional"))
    )
    (net (code "47") (name "BMB10") (class "Default")
      (node (ref "N15") (pin "T2") (pinfunction "1_T2") (pintype "bidirectional"))
    )
    (net (code "48") (name "BMB11") (class "Default")
      (node (ref "N15") (pin "V2") (pinfunction "1_V2") (pintype "bidirectional"))
    )
    (net (code "49") (name "BTS2") (class "Default")
      (node (ref "N14") (pin "S2") (pinfunction "1_S2") (pintype "bidirectional"))
    )
    (net (code "50") (name "BTS5") (class "Default")
      (node (ref "N14") (pin "T2") (pinfunction "1_T2") (pintype "bidirectional"))
    )
    (net (code "51") (name "CK_PULSE") (class "Default")
      (node (ref "E11") (pin "5") (pinfunction "I0_5") (pintype "input"))
      (node (ref "E3") (pin "8") (pinfunction "~{Q}_8") (pintype "output"))
      (node (ref "E39") (pin "10") (pinfunction "I1_10") (pintype "input"))
      (node (ref "E48") (pin "3") (pinfunction "CLK_3") (pintype "input"))
      (node (ref "E8") (pin "3") (pinfunction "CLK_3") (pintype "input"))
    )
    (net (code "52") (name "DIV3") (class "Default")
      (node (ref "IC3") (pin "2") (pinfunction "CLR_2") (pintype "input"))
      (node (ref "IC9") (pin "6") (pinfunction "O_6") (pintype "output"))
    )
    (net (code "53") (name "DIV11") (class "Default")
      (node (ref "IC5") (pin "2") (pinfunction "CLR_2") (pintype "input"))
      (node (ref "IC9") (pin "12") (pinfunction "O_12") (pintype "output"))
    )
    (net (code "54") (name "EIA_IN") (class "Default")
      (node (ref "E17") (pin "1") (pinfunction "I_1") (pintype "input"))
      (node (ref "J1") (pin "J") (pinfunction "8_J") (pintype "bidirectional"))
    )
    (net (code "55") (name "EIA_OUT") (class "Default")
      (node (ref "E32") (pin "3") (pinfunction "O_3") (pintype "output"))
      (node (ref "J1") (pin "F") (pinfunction "6_F") (pintype "bidirectional"))
    )
    (net (code "56") (name "ENAB") (class "Default")
      (node (ref "E24") (pin "2") (pinfunction "I1_2") (pintype "input"))
      (node (ref "E25") (pin "13") (pinfunction "I3_13") (pintype "input"))
      (node (ref "E28") (pin "4") (pinfunction "D_4") (pintype "input"))
      (node (ref "E29") (pin "9") (pinfunction "Q_9") (pintype "output"))
    )
    (net (code "57") (name "GND") (class "Default")
      (node (ref "C1") (pin "2") (pinfunction "2_2") (pintype "passive"))
      (node (ref "C10") (pin "2") (pinfunction "2_2") (pintype "passive"))
      (node (ref "C11") (pin "2") (pinfunction "2_2") (pintype "passive"))
      (node (ref "C12") (pin "2") (pinfunction "2_2") (pintype "passive"))
      (node (ref "C13") (pin "2") (pinfunction "2_2") (pintype "passive"))
      (node (ref "C14") (pin "2") (pinfunction "2_2") (pintype "passive"))
      (node (ref "C15") (pin "2") (pinfunction "2_2") (pintype "passive"))
      (node (ref "C16") (pin "2") (pinfunction "2_2") (pintype "passive"))
      (node (ref "C17") (pin "2") (pinfunction "2_2") (pintype "passive"))
      (node (ref "C18") (pin "2") (pinfunction "2_2") (pintype "passive"))
      (node (ref "C19") (pin "2") (pinfunction "2_2") (pintype "passive"))
      (node (ref "C2") (pin "2") (pinfunction "2_2") (pintype "passive"))
      (node (ref "C20") (pin "2") (pinfunction "2_2") (pintype "passive"))
      (node (ref "C21") (pin "2") (pinfunction "2_2") (pintype "passive"))
      (node (ref "C22") (pin "2") (pinfunction "2_2") (pintype "passive"))
      (node (ref "C23") (pin "2") (pinfunction "2_2") (pintype "passive"))
      (node (ref "C24") (pin "2") (pinfunction "2_2") (pintype "passive"))
      (node (ref "C25") (pin "2") (pinfunction "2_2") (pintype "passive"))
      (node (ref "C26") (pin "2") (pinfunction "2_2") (pintype "passive"))
      (node (ref "C27") (pin "2") (pinfunction "2_2") (pintype "passive"))
      (node (ref "C28") (pin "2") (pinfunction "2_2") (pintype "passive"))
      (node (ref "C29") (pin "2") (pinfunction "2_2") (pintype "passive"))
      (node (ref "C3") (pin "2") (pinfunction "2_2") (pintype "passive"))
      (node (ref "C30") (pin "2") (pinfunction "2_2") (pintype "passive"))
      (node (ref "C31") (pin "2") (pinfunction "2_2") (pintype "passive"))
      (node (ref "C32") (pin "2") (pinfunction "2_2") (pintype "passive"))
      (node (ref "C4") (pin "2") (pinfunction "2_2") (pintype "passive"))
      (node (ref "C5") (pin "2") (pinfunction "2_2") (pintype "passive"))
      (node (ref "C51") (pin "-") (pinfunction "-_-") (pintype "passive"))
      (node (ref "C52") (pin "-") (pinfunction "-_-") (pintype "passive"))
      (node (ref "C53") (pin "-") (pinfunction "-_-") (pintype "passive"))
      (node (ref "C56") (pin "-") (pinfunction "-_-") (pintype "passive"))
      (node (ref "C57") (pin "2") (pinfunction "2_2") (pintype "passive"))
      (node (ref "C6") (pin "2") (pinfunction "2_2") (pintype "passive"))
      (node (ref "C62") (pin "2") (pinfunction "2_2") (pintype "passive"))
      (node (ref "C66") (pin "-") (pinfunction "-_-") (pintype "passive"))
      (node (ref "C7") (pin "2") (pinfunction "2_2") (pintype "passive"))
      (node (ref "C8") (pin "2") (pinfunction "2_2") (pintype "passive"))
      (node (ref "C9") (pin "2") (pinfunction "2_2") (pintype "passive"))
      (node (ref "D2") (pin "C") (pinfunction "C_C") (pintype "passive"))
      (node (ref "D5") (pin "C") (pinfunction "C_C") (pintype "passive"))
      (node (ref "D8") (pin "A") (pinfunction "A_A") (pintype "passive"))
      (node (ref "DL1") (pin "2") (pinfunction "2_2") (pintype "passive"))
      (node (ref "E14") (pin "14") (pinfunction "CKA_14") (pintype "input"))
      (node (ref "E14") (pin "2") (pinfunction "R0(1)_2") (pintype "input"))
      (node (ref "E14") (pin "3") (pinfunction "R0(2)_3") (pintype "input"))
      (node (ref "E16") (pin "12") (pinfunction "D_12") (pintype "input"))
      (node (ref "E26") (pin "14") (pinfunction "I3_14") (pintype "input"))
      (node (ref "E26") (pin "15") (pinfunction "I2_15") (pintype "input"))
      (node (ref "E26") (pin "2") (pinfunction "I1_2") (pintype "input"))
      (node (ref "E26") (pin "3") (pinfunction "I0_3") (pintype "input"))
      (node (ref "E3") (pin "12") (pinfunction "D_12") (pintype "input"))
      (node (ref "E32") (pin "4") (pinfunction "I0_4") (pintype "input"))
      (node (ref "E32") (pin "5") (pinfunction "I1_5") (pintype "input"))
      (node (ref "E7") (pin "12") (pinfunction "D_12") (pintype "input"))
      (node (ref "E7") (pin "2") (pinfunction "D_2") (pintype "input"))
      (node (ref "IC4") (pin "12") (pinfunction "CLR_12") (pintype "input"))
      (node (ref "IC4") (pin "2") (pinfunction "CLR_2") (pintype "input"))
      (node (ref "IC5") (pin "12") (pinfunction "CLR_12") (pintype "input"))
      (node (ref "J1") (pin "A") (pinfunction "1_A") (pintype "bidirectional"))
      (node (ref "J1") (pin "B") (pinfunction "2_B") (pintype "bidirectional"))
      (node (ref "J1") (pin "C") (pinfunction "3_C") (pintype "bidirectional"))
      (node (ref "J1") (pin "UU") (pinfunction "39_UU") (pintype "bidirectional"))
      (node (ref "J1") (pin "VV") (pinfunction "40_VV") (pintype "bidirectional"))
      (node (ref "N14") (pin "A1") (pinfunction "1_A1") (pintype "bidirectional"))
      (node (ref "N14") (pin "C1") (pinfunction "1_C1") (pintype "bidirectional"))
      (node (ref "N14") (pin "C2") (pinfunction "1_C2") (pintype "bidirectional"))
      (node (ref "N14") (pin "F1") (pinfunction "1_F1") (pintype "bidirectional"))
      (node (ref "N14") (pin "F2") (pinfunction "1_F2") (pintype "bidirectional"))
      (node (ref "N14") (pin "J2") (pinfunction "1_J2") (pintype "bidirectional"))
      (node (ref "N14") (pin "K1") (pinfunction "1_K1") (pintype "bidirectional"))
      (node (ref "N14") (pin "L2") (pinfunction "1_L2") (pintype "bidirectional"))
      (node (ref "N14") (pin "N1") (pinfunction "1_N1") (pintype "bidirectional"))
      (node (ref "N14") (pin "N2") (pinfunction "1_N2") (pintype "bidirectional"))
      (node (ref "N14") (pin "R1") (pinfunction "1_R1") (pintype "bidirectional"))
      (node (ref "N14") (pin "R2") (pinfunction "1_R2") (pintype "bidirectional"))
      (node (ref "N14") (pin "T1") (pinfunction "1_T1") (pintype "bidirectional"))
      (node (ref "N14") (pin "U2") (pinfunction "1_U2") (pintype "bidirectional"))
      (node (ref "N15") (pin "A1") (pinfunction "1_A1") (pintype "bidirectional"))
      (node (ref "N15") (pin "C1") (pinfunction "1_C1") (pintype "bidirectional"))
      (node (ref "N15") (pin "C2") (pinfunction "1_C2") (pintype "bidirectional"))
      (node (ref "N15") (pin "F1") (pinfunction "1_F1") (pintype "bidirectional"))
      (node (ref "N15") (pin "F2") (pinfunction "1_F2") (pintype "bidirectional"))
      (node (ref "N15") (pin "J2") (pinfunction "1_J2") (pintype "bidirectional"))
      (node (ref "N15") (pin "K1") (pinfunction "1_K1") (pintype "bidirectional"))
      (node (ref "N15") (pin "L2") (pinfunction "1_L2") (pintype "bidirectional"))
      (node (ref "N15") (pin "N1") (pinfunction "1_N1") (pintype "bidirectional"))
      (node (ref "N15") (pin "N2") (pinfunction "1_N2") (pintype "bidirectional"))
      (node (ref "N15") (pin "R1") (pinfunction "1_R1") (pintype "bidirectional"))
      (node (ref "N15") (pin "R2") (pinfunction "1_R2") (pintype "bidirectional"))
      (node (ref "N15") (pin "T1") (pinfunction "1_T1") (pintype "bidirectional"))
      (node (ref "N15") (pin "U2") (pinfunction "1_U2") (pintype "bidirectional"))
      (node (ref "N16") (pin "A1") (pinfunction "1_A1") (pintype "bidirectional"))
      (node (ref "N16") (pin "C1") (pinfunction "1_C1") (pintype "bidirectional"))
      (node (ref "N16") (pin "C2") (pinfunction "1_C2") (pintype "bidirectional"))
      (node (ref "N16") (pin "F1") (pinfunction "1_F1") (pintype "bidirectional"))
      (node (ref "N16") (pin "F2") (pinfunction "1_F2") (pintype "bidirectional"))
      (node (ref "N16") (pin "J2") (pinfunction "1_J2") (pintype "bidirectional"))
      (node (ref "N16") (pin "K1") (pinfunction "1_K1") (pintype "bidirectional"))
      (node (ref "N16") (pin "L2") (pinfunction "1_L2") (pintype "bidirectional"))
      (node (ref "N16") (pin "N1") (pinfunction "1_N1") (pintype "bidirectional"))
      (node (ref "N16") (pin "N2") (pinfunction "1_N2") (pintype "bidirectional"))
      (node (ref "N16") (pin "R1") (pinfunction "1_R1") (pintype "bidirectional"))
      (node (ref "N16") (pin "R2") (pinfunction "1_R2") (pintype "bidirectional"))
      (node (ref "N16") (pin "T1") (pinfunction "1_T1") (pintype "bidirectional"))
      (node (ref "N16") (pin "U2") (pinfunction "1_U2") (pintype "bidirectional"))
      (node (ref "OSC") (pin "4") (pinfunction "GND_4") (pintype "power_in"))
      (node (ref "OSC2") (pin "7") (pinfunction "GND_7") (pintype "power_in"))
      (node (ref "R20") (pin "2") (pinfunction "2_2") (pintype "passive"))
      (node (ref "SV1") (pin "1") (pinfunction "1_1") (pintype "passive"))
      (node (ref "SV1") (pin "13") (pinfunction "13_13") (pintype "passive"))
      (node (ref "SV1") (pin "14") (pinfunction "14_14") (pintype "passive"))
      (node (ref "SV1") (pin "2") (pinfunction "2_2") (pintype "passive"))
      (node (ref "SV2") (pin "1") (pinfunction "1_1") (pintype "passive"))
      (node (ref "SV2") (pin "13") (pinfunction "13_13") (pintype "passive"))
      (node (ref "SV2") (pin "14") (pinfunction "14_14") (pintype "passive"))
      (node (ref "SV2") (pin "2") (pinfunction "2_2") (pintype "passive"))
      (node (ref "SV3") (pin "1") (pinfunction "1_1") (pintype "passive"))
      (node (ref "SV3") (pin "13") (pinfunction "13_13") (pintype "passive"))
      (node (ref "SV3") (pin "14") (pinfunction "14_14") (pintype "passive"))
      (node (ref "SV3") (pin "2") (pinfunction "2_2") (pintype "passive"))
    )
    (net (code "58") (name "INITIALIZE") (class "Default")
      (node (ref "E42") (pin "1") (pinfunction "I_1") (pintype "input"))
      (node (ref "N14") (pin "V2") (pinfunction "1_V2") (pintype "bidirectional"))
    )
    (net (code "59") (name "KCC") (class "Default")
      (node (ref "E27") (pin "5") (pinfunction "I0_5") (pintype "input"))
      (node (ref "E27") (pin "6") (pinfunction "I1_6") (pintype "input"))
      (node (ref "E9") (pin "4") (pinfunction "O_4") (pintype "output"))
    )
    (net (code "60") (name "KRS") (class "Default")
      (node (ref "E15") (pin "11") (pinfunction "I0_11") (pintype "input"))
      (node (ref "E15") (pin "3") (pinfunction "I1_3") (pintype "input"))
      (node (ref "E15") (pin "5") (pinfunction "I0_5") (pintype "input"))
      (node (ref "E15") (pin "9") (pinfunction "I1_9") (pintype "input"))
      (node (ref "E2") (pin "11") (pinfunction "I0_11") (pintype "input"))
      (node (ref "E2") (pin "3") (pinfunction "I1_3") (pintype "input"))
      (node (ref "E2") (pin "5") (pinfunction "I0_5") (pintype "input"))
      (node (ref "E2") (pin "9") (pinfunction "I1_9") (pintype "input"))
      (node (ref "E9") (pin "6") (pinfunction "O_6") (pintype "output"))
    )
    (net (code "61") (name "KSKP") (class "Default")
      (node (ref "E11") (pin "13") (pinfunction "O_13") (pintype "output"))
      (node (ref "E27") (pin "2") (pinfunction "I0_2") (pintype "input"))
      (node (ref "E27") (pin "3") (pinfunction "I1_3") (pintype "input"))
    )
    (net (code "62") (name "LAST_UNIT") (class "Default")
      (node (ref "E39") (pin "13") (pinfunction "I3_13") (pintype "input"))
      (node (ref "E8") (pin "5") (pinfunction "Q_5") (pintype "output"))
    )
    (net (code "63") (name "Net-(C66-Pad+)") (class "Default")
      (node (ref "C66") (pin "+") (pinfunction "+_+") (pintype "passive"))
      (node (ref "D7") (pin "A") (pinfunction "A_A") (pintype "passive"))
      (node (ref "D8") (pin "C") (pinfunction "C_C") (pintype "passive"))
      (node (ref "R18") (pin "1") (pinfunction "1_1") (pintype "passive"))
      (node (ref "R22") (pin "2") (pinfunction "2_2") (pintype "passive"))
    )
    (net (code "64") (name "Net-(D2-PadA)") (class "Default")
      (node (ref "D2") (pin "A") (pinfunction "A_A") (pintype "passive"))
      (node (ref "D3") (pin "C") (pinfunction "C_C") (pintype "passive"))
    )
    (net (code "65") (name "Net-(D3-PadA)") (class "Default")
      (node (ref "D3") (pin "A") (pinfunction "A_A") (pintype "passive"))
      (node (ref "D4") (pin "C") (pinfunction "C_C") (pintype "passive"))
    )
    (net (code "66") (name "Net-(D10-PadC)") (class "Default")
      (node (ref "D10") (pin "C") (pinfunction "C_C") (pintype "passive"))
      (node (ref "D11") (pin "A") (pinfunction "A_A") (pintype "passive"))
    )
    (net (code "67") (name "Net-(D11-PadC)") (class "Default")
      (node (ref "D11") (pin "C") (pinfunction "C_C") (pintype "passive"))
      (node (ref "D12") (pin "A") (pinfunction "A_A") (pintype "passive"))
    )
    (net (code "68") (name "Net-(D13-PadA)") (class "Default")
      (node (ref "D13") (pin "A") (pinfunction "A_A") (pintype "passive"))
      (node (ref "D14") (pin "C") (pinfunction "C_C") (pintype "passive"))
    )
    (net (code "69") (name "Net-(D14-PadA)") (class "Default")
      (node (ref "D14") (pin "A") (pinfunction "A_A") (pintype "passive"))
      (node (ref "D15") (pin "C") (pinfunction "C_C") (pintype "passive"))
    )
    (net (code "70") (name "Net-(E2B-I1)") (class "Default")
      (node (ref "E2") (pin "6") (pinfunction "I1_6") (pintype "input"))
      (node (ref "E6") (pin "9") (pinfunction "Q2_9") (pintype "output"))
    )
    (net (code "71") (name "Net-(E2C-I0)") (class "Default")
      (node (ref "E2") (pin "8") (pinfunction "I0_8") (pintype "input"))
      (node (ref "E6") (pin "7") (pinfunction "Q1_7") (pintype "output"))
    )
    (net (code "72") (name "Net-(E8B-D)") (class "Default")
      (node (ref "E8") (pin "12") (pinfunction "D_12") (pintype "input"))
      (node (ref "E8") (pin "8") (pinfunction "~{Q}_8") (pintype "output"))
    )
    (net (code "73") (name "Net-(E9A-I)") (class "Default")
      (node (ref "E9") (pin "1") (pinfunction "I_1") (pintype "input"))
      (node (ref "IC1") (pin "8") (pinfunction "O_8") (pintype "output"))
    )
    (net (code "74") (name "Net-(E9F-I)") (class "Default")
      (node (ref "E9") (pin "13") (pinfunction "I_13") (pintype "input"))
      (node (ref "IC2") (pin "8") (pinfunction "O_8") (pintype "output"))
    )
    (net (code "75") (name "Net-(E10A-C)") (class "Default")
      (node (ref "E10") (pin "6") (pinfunction "C_6") (pintype "input"))
      (node (ref "E11") (pin "4") (pinfunction "O_4") (pintype "output"))
      (node (ref "E6") (pin "6") (pinfunction "C_6") (pintype "input"))
    )
    (net (code "76") (name "Net-(E10A-D)") (class "Default")
      (node (ref "E10") (pin "4") (pinfunction "D_4") (pintype "input"))
      (node (ref "E2") (pin "2") (pinfunction "I0_2") (pintype "input"))
      (node (ref "E6") (pin "11") (pinfunction "Q3_11") (pintype "output"))
    )
    (net (code "77") (name "Net-(E10A-Q0)") (class "Default")
      (node (ref "E10") (pin "5") (pinfunction "Q0_5") (pintype "output"))
      (node (ref "E15") (pin "12") (pinfunction "I1_12") (pintype "input"))
    )
    (net (code "78") (name "Net-(E10A-Q1)") (class "Default")
      (node (ref "E10") (pin "7") (pinfunction "Q1_7") (pintype "output"))
      (node (ref "E15") (pin "8") (pinfunction "I0_8") (pintype "input"))
    )
    (net (code "79") (name "Net-(E10A-Q2)") (class "Default")
      (node (ref "E10") (pin "9") (pinfunction "Q2_9") (pintype "output"))
      (node (ref "E15") (pin "6") (pinfunction "I1_6") (pintype "input"))
    )
    (net (code "80") (name "Net-(E10A-Q3)") (class "Default")
      (node (ref "E10") (pin "11") (pinfunction "Q3_11") (pintype "output"))
      (node (ref "E15") (pin "2") (pinfunction "I0_2") (pintype "input"))
    )
    (net (code "81") (name "Net-(E11A-O)") (class "Default")
      (node (ref "E11") (pin "1") (pinfunction "O_1") (pintype "output"))
      (node (ref "E39") (pin "9") (pinfunction "I2_9") (pintype "input"))
    )
    (net (code "82") (name "Net-(E11B-I1)") (class "Default")
      (node (ref "E11") (pin "10") (pinfunction "O_10") (pintype "output"))
      (node (ref "E11") (pin "6") (pinfunction "I1_6") (pintype "input"))
    )
    (net (code "83") (name "Net-(E12B-O)") (class "Default")
      (node (ref "E12") (pin "6") (pinfunction "O_6") (pintype "output"))
      (node (ref "E8") (pin "1") (pinfunction "CLR_1") (pintype "input"))
    )
    (net (code "84") (name "Net-(E12C-O)") (class "Default")
      (node (ref "E12") (pin "8") (pinfunction "O_8") (pintype "output"))
      (node (ref "E3") (pin "2") (pinfunction "D_2") (pintype "input"))
    )
    (net (code "85") (name "Net-(E13A-D)") (class "Default")
      (node (ref "E13") (pin "2") (pinfunction "D_2") (pintype "input"))
      (node (ref "E40") (pin "11") (pinfunction "O_11") (pintype "output"))
    )
    (net (code "86") (name "Net-(E13B-PRE)") (class "Default")
      (node (ref "E13") (pin "10") (pinfunction "PRE_10") (pintype "input"))
      (node (ref "E42") (pin "6") (pinfunction "O_6") (pintype "output"))
    )
    (net (code "87") (name "Net-(E17A-O)") (class "Default")
      (node (ref "E17") (pin "3") (pinfunction "O_3") (pintype "output"))
      (node (ref "E21") (pin "5") (pinfunction "I_5") (pintype "input"))
    )
    (net (code "88") (name "Net-(E17A-RC)") (class "Default")
      (node (ref "E17") (pin "2") (pinfunction "RC_2") (pintype "input"))
      (node (ref "R23") (pin "1") (pinfunction "1_1") (pintype "passive"))
    )
    (net (code "89") (name "Net-(E19A-O)") (class "Default")
      (node (ref "E19") (pin "12") (pinfunction "O_12") (pintype "output"))
      (node (ref "E42") (pin "5") (pinfunction "I_5") (pintype "input"))
    )
    (net (code "90") (name "Net-(E19B-I0)") (class "Default")
      (node (ref "E19") (pin "11") (pinfunction "I2_11") (pintype "input"))
      (node (ref "E19") (pin "3") (pinfunction "I0_3") (pintype "input"))
      (node (ref "E24") (pin "8") (pinfunction "O_8") (pintype "output"))
    )
    (net (code "91") (name "Net-(E19B-I2)") (class "Default")
      (node (ref "E19") (pin "10") (pinfunction "I1_10") (pintype "input"))
      (node (ref "E19") (pin "5") (pinfunction "I2_5") (pintype "input"))
      (node (ref "E19") (pin "9") (pinfunction "I0_9") (pintype "input"))
      (node (ref "E24") (pin "6") (pinfunction "O_6") (pintype "output"))
    )
    (net (code "92") (name "Net-(E20A-D)") (class "Default")
      (node (ref "E20") (pin "2") (pinfunction "D_2") (pintype "input"))
      (node (ref "E25") (pin "8") (pinfunction "O_8") (pintype "output"))
    )
    (net (code "93") (name "Net-(E21A-I)") (class "Default")
      (node (ref "E21") (pin "1") (pinfunction "I_1") (pintype "input"))
      (node (ref "E39") (pin "8") (pinfunction "O_8") (pintype "output"))
    )
    (net (code "94") (name "Net-(E21A-O)") (class "Default")
      (node (ref "E21") (pin "2") (pinfunction "O_2") (pintype "output"))
      (node (ref "E7") (pin "3") (pinfunction "CLK_3") (pintype "input"))
    )
    (net (code "95") (name "Net-(E21B-O)") (class "Default")
      (node (ref "E21") (pin "4") (pinfunction "O_4") (pintype "output"))
      (node (ref "E3") (pin "11") (pinfunction "CLK_11") (pintype "input"))
    )
    (net (code "96") (name "Net-(E21D-O)") (class "Default")
      (node (ref "E21") (pin "8") (pinfunction "O_8") (pintype "output"))
      (node (ref "E6") (pin "4") (pinfunction "D_4") (pintype "input"))
    )
    (net (code "97") (name "Net-(E21E-O)") (class "Default")
      (node (ref "E21") (pin "10") (pinfunction "O_10") (pintype "output"))
      (node (ref "E5") (pin "2") (pinfunction "I1_2") (pintype "input"))
    )
    (net (code "98") (name "Net-(E21F-O)") (class "Default")
      (node (ref "E21") (pin "12") (pinfunction "O_12") (pintype "output"))
      (node (ref "E48") (pin "11") (pinfunction "CLK_11") (pintype "input"))
    )
    (net (code "99") (name "Net-(E23D-O)") (class "Default")
      (node (ref "E23") (pin "11") (pinfunction "O_11") (pintype "output"))
      (node (ref "E9") (pin "11") (pinfunction "I_11") (pintype "input"))
    )
    (net (code "100") (name "Net-(E24A-I0)") (class "Default")
      (node (ref "E24") (pin "1") (pinfunction "I0_1") (pintype "input"))
      (node (ref "E28") (pin "9") (pinfunction "Q2_9") (pintype "output"))
    )
    (net (code "101") (name "Net-(E24A-I2)") (class "Default")
      (node (ref "E24") (pin "4") (pinfunction "I2_4") (pintype "input"))
      (node (ref "E28") (pin "5") (pinfunction "Q0_5") (pintype "output"))
    )
    (net (code "102") (name "Net-(E24A-I3)") (class "Default")
      (node (ref "E24") (pin "5") (pinfunction "I3_5") (pintype "input"))
      (node (ref "E28") (pin "7") (pinfunction "Q1_7") (pintype "output"))
    )
    (net (code "103") (name "Net-(E24B-I0)") (class "Default")
      (node (ref "E24") (pin "9") (pinfunction "I0_9") (pintype "input"))
      (node (ref "E31") (pin "5") (pinfunction "Q0_5") (pintype "output"))
    )
    (net (code "104") (name "Net-(E24B-I1)") (class "Default")
      (node (ref "E24") (pin "10") (pinfunction "I1_10") (pintype "input"))
      (node (ref "E31") (pin "7") (pinfunction "Q1_7") (pintype "output"))
    )
    (net (code "105") (name "Net-(E24B-I2)") (class "Default")
      (node (ref "E24") (pin "12") (pinfunction "I2_12") (pintype "input"))
      (node (ref "E31") (pin "9") (pinfunction "Q2_9") (pintype "output"))
    )
    (net (code "106") (name "Net-(E24B-I3)") (class "Default")
      (node (ref "E24") (pin "13") (pinfunction "I3_13") (pintype "input"))
      (node (ref "E28") (pin "11") (pinfunction "Q3_11") (pintype "output"))
      (node (ref "E31") (pin "4") (pinfunction "D_4") (pintype "input"))
    )
    (net (code "107") (name "Net-(E25B-I4)") (class "Default")
      (node (ref "DL1") (pin "3") (pinfunction "3_3") (pintype "passive"))
      (node (ref "E25") (pin "5") (pinfunction "I4_5") (pintype "input"))
      (node (ref "R20") (pin "1") (pinfunction "1_1") (pintype "passive"))
    )
    (net (code "108") (name "Net-(E26A-C)") (class "Default")
      (node (ref "E26") (pin "6") (pinfunction "C_6") (pintype "input"))
      (node (ref "E42") (pin "8") (pinfunction "O_8") (pintype "output"))
    )
    (net (code "109") (name "Net-(E26A-Q0)") (class "Default")
      (node (ref "E26") (pin "5") (pinfunction "Q0_5") (pintype "output"))
      (node (ref "J23") (pin "3") (pinfunction "3_3") (pintype "passive"))
    )
    (net (code "110") (name "Net-(E26A-Q2)") (class "Default")
      (node (ref "E26") (pin "9") (pinfunction "Q2_9") (pintype "output"))
      (node (ref "J23") (pin "1") (pinfunction "1_1") (pintype "passive"))
      (node (ref "JJ23") (pin "1") (pinfunction "1_1") (pintype "passive"))
    )
    (net (code "111") (name "Net-(E27D-I0)") (class "Default")
      (node (ref "E27") (pin "11") (pinfunction "I0_11") (pintype "input"))
      (node (ref "E27") (pin "12") (pinfunction "I1_12") (pintype "input"))
      (node (ref "E45") (pin "13") (pinfunction "O_13") (pintype "output"))
    )
    (net (code "112") (name "Net-(E29B-CLK)") (class "Default")
      (node (ref "E29") (pin "11") (pinfunction "CLK_11") (pintype "input"))
      (node (ref "E42") (pin "4") (pinfunction "O_4") (pintype "output"))
    )
    (net (code "113") (name "Net-(E32A-I)") (class "Default")
      (node (ref "E32") (pin "2") (pinfunction "I_2") (pintype "input"))
      (node (ref "E9") (pin "8") (pinfunction "O_8") (pintype "output"))
    )
    (net (code "114") (name "Net-(E36B-I0)") (class "Default")
      (node (ref "C65") (pin "1") (pinfunction "1_1") (pintype "passive"))
      (node (ref "E36") (pin "6") (pinfunction "I0_6") (pintype "input"))
      (node (ref "E36") (pin "7") (pinfunction "I1_7") (pintype "input"))
      (node (ref "R18") (pin "2") (pinfunction "2_2") (pintype "passive"))
      (node (ref "R19") (pin "1") (pinfunction "1_1") (pintype "passive"))
    )
    (net (code "115") (name "Net-(E48A-CLR)") (class "Default")
      (node (ref "E48") (pin "1") (pinfunction "CLR_1") (pintype "input"))
      (node (ref "E9") (pin "10") (pinfunction "O_10") (pintype "output"))
    )
    (net (code "116") (name "Net-(IC1A-I2)") (class "Default")
      (node (ref "IC1") (pin "3") (pinfunction "I2_3") (pintype "input"))
      (node (ref "RX3") (pin "2") (pinfunction "2_2") (pintype "passive"))
    )
    (net (code "117") (name "Net-(IC1A-I3)") (class "Default")
      (node (ref "IC1") (pin "4") (pinfunction "I3_4") (pintype "input"))
      (node (ref "RX4") (pin "2") (pinfunction "2_2") (pintype "passive"))
    )
    (net (code "118") (name "Net-(IC1A-I4)") (class "Default")
      (node (ref "IC1") (pin "5") (pinfunction "I4_5") (pintype "input"))
      (node (ref "RX5") (pin "2") (pinfunction "2_2") (pintype "passive"))
    )
    (net (code "119") (name "Net-(IC1A-I5)") (class "Default")
      (node (ref "IC1") (pin "6") (pinfunction "I5_6") (pintype "input"))
      (node (ref "RX6") (pin "2") (pinfunction "2_2") (pintype "passive"))
    )
    (net (code "120") (name "Net-(IC1A-I6)") (class "Default")
      (node (ref "IC1") (pin "11") (pinfunction "I6_11") (pintype "input"))
      (node (ref "RX7") (pin "2") (pinfunction "2_2") (pintype "passive"))
    )
    (net (code "121") (name "Net-(IC1A-I7)") (class "Default")
      (node (ref "IC1") (pin "12") (pinfunction "I7_12") (pintype "input"))
      (node (ref "RX8") (pin "2") (pinfunction "2_2") (pintype "passive"))
    )
    (net (code "122") (name "Net-(IC2A-I2)") (class "Default")
      (node (ref "IC2") (pin "3") (pinfunction "I2_3") (pintype "input"))
      (node (ref "TX3") (pin "2") (pinfunction "2_2") (pintype "passive"))
    )
    (net (code "123") (name "Net-(IC2A-I3)") (class "Default")
      (node (ref "IC2") (pin "4") (pinfunction "I3_4") (pintype "input"))
      (node (ref "TX4") (pin "2") (pinfunction "2_2") (pintype "passive"))
    )
    (net (code "124") (name "Net-(IC2A-I4)") (class "Default")
      (node (ref "IC2") (pin "5") (pinfunction "I4_5") (pintype "input"))
      (node (ref "TX5") (pin "2") (pinfunction "2_2") (pintype "passive"))
    )
    (net (code "125") (name "Net-(IC2A-I5)") (class "Default")
      (node (ref "IC2") (pin "6") (pinfunction "I5_6") (pintype "input"))
      (node (ref "TX6") (pin "2") (pinfunction "2_2") (pintype "passive"))
    )
    (net (code "126") (name "Net-(IC2A-I6)") (class "Default")
      (node (ref "IC2") (pin "11") (pinfunction "I6_11") (pintype "input"))
      (node (ref "TX7") (pin "2") (pinfunction "2_2") (pintype "passive"))
    )
    (net (code "127") (name "Net-(IC2A-I7)") (class "Default")
      (node (ref "IC2") (pin "12") (pinfunction "I7_12") (pintype "input"))
      (node (ref "TX8") (pin "2") (pinfunction "2_2") (pintype "passive"))
    )
    (net (code "128") (name "Net-(IC5A-QA)") (class "Default")
      (node (ref "IC5") (pin "3") (pinfunction "QA_3") (pintype "output"))
      (node (ref "IC9") (pin "2") (pinfunction "I1_2") (pintype "input"))
    )
    (net (code "129") (name "Net-(IC5A-QB)") (class "Default")
      (node (ref "IC5") (pin "4") (pinfunction "QB_4") (pintype "output"))
      (node (ref "IC9") (pin "1") (pinfunction "I0_1") (pintype "input"))
    )
    (net (code "130") (name "Net-(Q2-E)") (class "Default")
      (node (ref "D4") (pin "A") (pinfunction "A_A") (pintype "passive"))
      (node (ref "Q2") (pin "1") (pinfunction "E_1") (pintype "passive"))
      (node (ref "R8") (pin "1") (pinfunction "1_1") (pintype "passive"))
    )
    (net (code "131") (name "Net-(Q3-B)") (class "Default")
      (node (ref "C63") (pin "1") (pinfunction "1_1") (pintype "passive"))
      (node (ref "Q3") (pin "2") (pinfunction "B_2") (pintype "passive"))
      (node (ref "R13") (pin "2") (pinfunction "2_2") (pintype "passive"))
    )
    (net (code "132") (name "Net-(Q3-C)") (class "Default")
      (node (ref "C63") (pin "2") (pinfunction "2_2") (pintype "passive"))
      (node (ref "D9") (pin "A") (pinfunction "A_A") (pintype "passive"))
      (node (ref "Q3") (pin "3") (pinfunction "C_3") (pintype "passive"))
      (node (ref "R12") (pin "2") (pinfunction "2_2") (pintype "passive"))
    )
    (net (code "133") (name "READER_RUN+") (class "Default")
      (node (ref "C62") (pin "1") (pinfunction "1_1") (pintype "passive"))
      (node (ref "D5") (pin "A") (pinfunction "A_A") (pintype "passive"))
      (node (ref "J1") (pin "PP") (pinfunction "35_PP") (pintype "bidirectional"))
      (node (ref "Q2") (pin "3") (pinfunction "C_3") (pintype "passive"))
    )
    (net (code "134") (name "READER_RUN-") (class "Default")
      (node (ref "J1") (pin "EE") (pinfunction "27_EE") (pintype "bidirectional"))
      (node (ref "R9") (pin "2") (pinfunction "2_2") (pintype "passive"))
    )
    (net (code "135") (name "RFLG") (class "Default")
      (node (ref "E33") (pin "2") (pinfunction "I0_2") (pintype "input"))
      (node (ref "E33") (pin "3") (pinfunction "I1_3") (pintype "input"))
      (node (ref "E48") (pin "5") (pinfunction "Q_5") (pintype "output"))
    )
    (net (code "136") (name "RTS") (class "Default")
      (node (ref "E32") (pin "8") (pinfunction "O_8") (pintype "output"))
      (node (ref "J1") (pin "V") (pinfunction "18_V") (pintype "bidirectional"))
    )
    (net (code "137") (name "RTSDTR") (class "Default")
      (node (ref "E32") (pin "6") (pinfunction "O_6") (pintype "output"))
      (node (ref "J1") (pin "DD") (pinfunction "26_DD") (pintype "bidirectional"))
    )
    (net (code "138") (name "RUN") (class "Default")
      (node (ref "N16") (pin "S2") (pinfunction "1_S2") (pintype "bidirectional"))
    )
    (net (code "139") (name "RX7") (class "Default")
      (node (ref "E2") (pin "12") (pinfunction "I1_12") (pintype "input"))
      (node (ref "E21") (pin "13") (pinfunction "I_13") (pintype "input"))
      (node (ref "E6") (pin "5") (pinfunction "Q0_5") (pintype "output"))
      (node (ref "R24") (pin "1") (pinfunction "1_1") (pintype "passive"))
    )
    (net (code "140") (name "RX20MA_DATA") (class "Default")
      (node (ref "C65") (pin "2") (pinfunction "2_2") (pintype "passive"))
      (node (ref "E36") (pin "2") (pinfunction "O_2") (pintype "output"))
      (node (ref "J1") (pin "H") (pinfunction "7_H") (pintype "bidirectional"))
      (node (ref "R19") (pin "2") (pinfunction "2_2") (pintype "passive"))
    )
    (net (code "141") (name "RX_20MA+") (class "Default")
      (node (ref "C64") (pin "1") (pinfunction "1_1") (pintype "passive"))
      (node (ref "J1") (pin "K") (pinfunction "9_K") (pintype "bidirectional"))
      (node (ref "R16") (pin "1") (pinfunction "1_1") (pintype "passive"))
      (node (ref "R22") (pin "1") (pinfunction "1_1") (pintype "passive"))
    )
    (net (code "142") (name "RX_20MA-") (class "Default")
      (node (ref "C64") (pin "2") (pinfunction "2_2") (pintype "passive"))
      (node (ref "J1") (pin "S") (pinfunction "15_S") (pintype "bidirectional"))
      (node (ref "R17") (pin "2") (pinfunction "2_2") (pintype "passive"))
    )
    (net (code "143") (name "RX_ACTIVE") (class "Default")
      (node (ref "E12") (pin "1") (pinfunction "I0_1") (pintype "input"))
      (node (ref "E7") (pin "11") (pinfunction "CLK_11") (pintype "input"))
      (node (ref "E7") (pin "5") (pinfunction "Q_5") (pintype "output"))
    )
    (net (code "144") (name "RX_BOT") (class "Default")
      (node (ref "E10") (pin "12") (pinfunction "Q4_12") (pintype "output"))
      (node (ref "E48") (pin "2") (pinfunction "D_2") (pintype "input"))
      (node (ref "E8") (pin "2") (pinfunction "D_2") (pintype "input"))
    )
    (net (code "145") (name "RX_DATA") (class "Default")
      (node (ref "E21") (pin "6") (pinfunction "O_6") (pintype "output"))
      (node (ref "J1") (pin "M") (pinfunction "11_M") (pintype "bidirectional"))
    )
    (net (code "146") (name "RX_DIV") (class "Default")
      (node (ref "E12") (pin "9") (pinfunction "I0_9") (pintype "input"))
      (node (ref "E3") (pin "5") (pinfunction "Q_5") (pintype "output"))
    )
    (net (code "147") (name "RX_DIV8") (class "Default")
      (node (ref "E12") (pin "2") (pinfunction "I1_2") (pintype "input"))
      (node (ref "E12") (pin "5") (pinfunction "I1_5") (pintype "input"))
      (node (ref "E8") (pin "9") (pinfunction "Q_9") (pintype "output"))
    )
    (net (code "148") (name "RX_DONE") (class "Default")
      (node (ref "E36") (pin "3") (pinfunction "O_3") (pintype "output"))
      (node (ref "E4") (pin "1") (pinfunction "CLR_1") (pintype "input"))
      (node (ref "E4") (pin "13") (pinfunction "CLR_13") (pintype "input"))
      (node (ref "E8") (pin "13") (pinfunction "CLR_13") (pintype "input"))
    )
    (net (code "149") (name "RX_RATE") (class "Default")
      (node (ref "E14") (pin "1") (pinfunction "CKB_1") (pintype "input"))
      (node (ref "E3") (pin "10") (pinfunction "PRE_10") (pintype "input"))
      (node (ref "E3") (pin "3") (pinfunction "CLK_3") (pintype "input"))
      (node (ref "E5") (pin "13") (pinfunction "I2_13") (pintype "input"))
      (node (ref "J2") (pin "3") (pinfunction "3_3") (pintype "passive"))
      (node (ref "SV1") (pin "8") (pinfunction "8_8") (pintype "passive"))
      (node (ref "SV2") (pin "8") (pinfunction "8_8") (pintype "passive"))
      (node (ref "SV3") (pin "8") (pinfunction "8_8") (pintype "passive"))
    )
    (net (code "150") (name "RX_SEL") (class "Default")
      (node (ref "E23") (pin "2") (pinfunction "I1_2") (pintype "input"))
      (node (ref "E23") (pin "4") (pinfunction "I0_4") (pintype "input"))
      (node (ref "E23") (pin "9") (pinfunction "I0_9") (pintype "input"))
      (node (ref "E9") (pin "2") (pinfunction "O_2") (pintype "output"))
      (node (ref "SV1") (pin "12") (pinfunction "12_12") (pintype "passive"))
      (node (ref "SV2") (pin "12") (pinfunction "12_12") (pintype "passive"))
      (node (ref "SV3") (pin "12") (pinfunction "12_12") (pintype "passive"))
    )
    (net (code "151") (name "SERIAL_IN") (class "Default")
      (node (ref "E11") (pin "3") (pinfunction "I1_3") (pintype "input"))
      (node (ref "E21") (pin "9") (pinfunction "I_9") (pintype "input"))
      (node (ref "E5") (pin "1") (pinfunction "I0_1") (pintype "input"))
      (node (ref "J1") (pin "E") (pinfunction "5_E") (pintype "bidirectional"))
    )
    (net (code "152") (name "STP_MARK") (class "Default")
      (node (ref "E25") (pin "1") (pinfunction "I4_1") (pintype "input"))
      (node (ref "J23") (pin "2") (pinfunction "2_2") (pintype "passive"))
      (node (ref "JJ23") (pin "2") (pinfunction "2_2") (pintype "passive"))
    )
    (net (code "153") (name "TFLG") (class "Default")
      (node (ref "E13") (pin "8") (pinfunction "~{Q}_8") (pintype "output"))
      (node (ref "E27") (pin "8") (pinfunction "I0_8") (pintype "input"))
      (node (ref "E27") (pin "9") (pinfunction "I1_9") (pintype "input"))
    )
    (net (code "154") (name "TPC") (class "Default")
      (node (ref "E25") (pin "2") (pinfunction "I1_2") (pintype "input"))
      (node (ref "E25") (pin "3") (pinfunction "I2_3") (pintype "input"))
      (node (ref "E29") (pin "12") (pinfunction "D_12") (pintype "input"))
      (node (ref "E42") (pin "10") (pinfunction "O_10") (pintype "output"))
    )
    (net (code "155") (name "TX7") (class "Default")
      (node (ref "E13") (pin "12") (pinfunction "D_12") (pintype "input"))
      (node (ref "E19") (pin "8") (pinfunction "O_8") (pintype "output"))
    )
    (net (code "156") (name "TX8") (class "Default")
      (node (ref "E19") (pin "6") (pinfunction "O_6") (pintype "output"))
      (node (ref "E25") (pin "10") (pinfunction "I1_10") (pintype "input"))
    )
    (net (code "157") (name "TX_20MA+") (class "Default")
      (node (ref "D6") (pin "C") (pinfunction "C_C") (pintype "passive"))
      (node (ref "D9") (pin "C") (pinfunction "C_C") (pintype "passive"))
      (node (ref "J1") (pin "AA") (pinfunction "23_AA") (pintype "bidirectional"))
      (node (ref "R25") (pin "2") (pinfunction "2_2") (pintype "passive"))
    )
    (net (code "158") (name "TX_20MA-") (class "Default")
      (node (ref "J1") (pin "KK") (pinfunction "31_KK") (pintype "bidirectional"))
      (node (ref "R11") (pin "2") (pinfunction "2_2") (pintype "passive"))
    )
    (net (code "159") (name "TX_ACTIVE") (class "Default")
      (node (ref "E20") (pin "11") (pinfunction "CLK_11") (pintype "input"))
      (node (ref "E20") (pin "6") (pinfunction "~{Q}_6") (pintype "output"))
      (node (ref "E25") (pin "9") (pinfunction "I2_9") (pintype "input"))
      (node (ref "E29") (pin "4") (pinfunction "PRE_4") (pintype "input"))
      (node (ref "E40") (pin "13") (pinfunction "I1_13") (pintype "input"))
    )
    (net (code "160") (name "TX_DATA") (class "Default")
      (node (ref "E29") (pin "2") (pinfunction "D_2") (pintype "input"))
      (node (ref "E31") (pin "11") (pinfunction "Q3_11") (pintype "output"))
    )
    (net (code "161") (name "TX_DIV") (class "Default")
      (node (ref "E13") (pin "11") (pinfunction "CLK_11") (pintype "input"))
      (node (ref "E13") (pin "5") (pinfunction "Q_5") (pintype "output"))
      (node (ref "E25") (pin "4") (pinfunction "I3_4") (pintype "input"))
      (node (ref "E26") (pin "1") (pinfunction "R_1") (pintype "input"))
      (node (ref "E29") (pin "3") (pinfunction "CLK_3") (pintype "input"))
      (node (ref "E40") (pin "12") (pinfunction "I0_12") (pintype "input"))
    )
    (net (code "162") (name "TX_RATE") (class "Default")
      (node (ref "E13") (pin "3") (pinfunction "CLK_3") (pintype "input"))
      (node (ref "E14") (pin "11") (pinfunction "QD_11") (pintype "output"))
      (node (ref "E20") (pin "13") (pinfunction "CLR_13") (pintype "input"))
      (node (ref "E20") (pin "3") (pinfunction "CLK_3") (pintype "input"))
      (node (ref "E42") (pin "9") (pinfunction "I_9") (pintype "input"))
      (node (ref "J2") (pin "1") (pinfunction "1_1") (pintype "passive"))
      (node (ref "J2") (pin "2") (pinfunction "2_2") (pintype "passive"))
    )
    (net (code "163") (name "TX_SEL") (class "Default")
      (node (ref "E40") (pin "2") (pinfunction "I1_2") (pintype "input"))
      (node (ref "E40") (pin "4") (pinfunction "I0_4") (pintype "input"))
      (node (ref "E40") (pin "9") (pinfunction "I0_9") (pintype "input"))
      (node (ref "E9") (pin "12") (pinfunction "O_12") (pintype "output"))
      (node (ref "SV1") (pin "11") (pinfunction "11_11") (pintype "passive"))
      (node (ref "SV2") (pin "11") (pinfunction "11_11") (pintype "passive"))
      (node (ref "SV3") (pin "11") (pinfunction "11_11") (pintype "passive"))
    )
    (net (code "164") (name "VCC") (class "Default")
      (node (ref "C1") (pin "1") (pinfunction "1_1") (pintype "passive"))
      (node (ref "C10") (pin "1") (pinfunction "1_1") (pintype "passive"))
      (node (ref "C11") (pin "1") (pinfunction "1_1") (pintype "passive"))
      (node (ref "C12") (pin "1") (pinfunction "1_1") (pintype "passive"))
      (node (ref "C13") (pin "1") (pinfunction "1_1") (pintype "passive"))
      (node (ref "C14") (pin "1") (pinfunction "1_1") (pintype "passive"))
      (node (ref "C15") (pin "1") (pinfunction "1_1") (pintype "passive"))
      (node (ref "C16") (pin "1") (pinfunction "1_1") (pintype "passive"))
      (node (ref "C17") (pin "1") (pinfunction "1_1") (pintype "passive"))
      (node (ref "C18") (pin "1") (pinfunction "1_1") (pintype "passive"))
      (node (ref "C19") (pin "1") (pinfunction "1_1") (pintype "passive"))
      (node (ref "C2") (pin "1") (pinfunction "1_1") (pintype "passive"))
      (node (ref "C20") (pin "1") (pinfunction "1_1") (pintype "passive"))
      (node (ref "C21") (pin "1") (pinfunction "1_1") (pintype "passive"))
      (node (ref "C22") (pin "1") (pinfunction "1_1") (pintype "passive"))
      (node (ref "C23") (pin "1") (pinfunction "1_1") (pintype "passive"))
      (node (ref "C24") (pin "1") (pinfunction "1_1") (pintype "passive"))
      (node (ref "C25") (pin "1") (pinfunction "1_1") (pintype "passive"))
      (node (ref "C26") (pin "1") (pinfunction "1_1") (pintype "passive"))
      (node (ref "C27") (pin "1") (pinfunction "1_1") (pintype "passive"))
      (node (ref "C28") (pin "1") (pinfunction "1_1") (pintype "passive"))
      (node (ref "C29") (pin "1") (pinfunction "1_1") (pintype "passive"))
      (node (ref "C3") (pin "1") (pinfunction "1_1") (pintype "passive"))
      (node (ref "C30") (pin "1") (pinfunction "1_1") (pintype "passive"))
      (node (ref "C31") (pin "1") (pinfunction "1_1") (pintype "passive"))
      (node (ref "C4") (pin "1") (pinfunction "1_1") (pintype "passive"))
      (node (ref "C5") (pin "1") (pinfunction "1_1") (pintype "passive"))
      (node (ref "C51") (pin "+") (pinfunction "+_+") (pintype "passive"))
      (node (ref "C52") (pin "+") (pinfunction "+_+") (pintype "passive"))
      (node (ref "C53") (pin "+") (pinfunction "+_+") (pintype "passive"))
      (node (ref "C56") (pin "+") (pinfunction "+_+") (pintype "passive"))
      (node (ref "C57") (pin "1") (pinfunction "1_1") (pintype "passive"))
      (node (ref "C6") (pin "1") (pinfunction "1_1") (pintype "passive"))
      (node (ref "C7") (pin "1") (pinfunction "1_1") (pintype "passive"))
      (node (ref "C8") (pin "1") (pinfunction "1_1") (pintype "passive"))
      (node (ref "C9") (pin "1") (pinfunction "1_1") (pintype "passive"))
      (node (ref "D7") (pin "C") (pinfunction "C_C") (pintype "passive"))
      (node (ref "E10") (pin "1") (pinfunction "R_1") (pintype "input"))
      (node (ref "E10") (pin "10") (pinfunction "L_10") (pintype "input"))
      (node (ref "E10") (pin "14") (pinfunction "I3_14") (pintype "input"))
      (node (ref "E10") (pin "15") (pinfunction "I2_15") (pintype "input"))
      (node (ref "E10") (pin "2") (pinfunction "I1_2") (pintype "input"))
      (node (ref "E10") (pin "3") (pinfunction "I0_3") (pintype "input"))
      (node (ref "E13") (pin "1") (pinfunction "CLR_1") (pintype "input"))
      (node (ref "E13") (pin "13") (pinfunction "CLR_13") (pintype "input"))
      (node (ref "E20") (pin "1") (pinfunction "CLR_1") (pintype "input"))
      (node (ref "E20") (pin "10") (pinfunction "PRE_10") (pintype "input"))
      (node (ref "E20") (pin "12") (pinfunction "D_12") (pintype "input"))
      (node (ref "E26") (pin "10") (pinfunction "L_10") (pintype "input"))
      (node (ref "E26") (pin "13") (pinfunction "S_13") (pintype "input"))
      (node (ref "E28") (pin "10") (pinfunction "L_10") (pintype "input"))
      (node (ref "E29") (pin "10") (pinfunction "PRE_10") (pintype "input"))
      (node (ref "E3") (pin "1") (pinfunction "CLR_1") (pintype "input"))
      (node (ref "E3") (pin "13") (pinfunction "CLR_13") (pintype "input"))
      (node (ref "E3") (pin "4") (pinfunction "PRE_4") (pintype "input"))
      (node (ref "E31") (pin "10") (pinfunction "L_10") (pintype "input"))
      (node (ref "E4") (pin "10") (pinfunction "PRE_10") (pintype "input"))
      (node (ref "E4") (pin "4") (pinfunction "PRE_4") (pintype "input"))
      (node (ref "E48") (pin "12") (pinfunction "D_12") (pintype "input"))
      (node (ref "E48") (pin "4") (pinfunction "PRE_4") (pintype "input"))
      (node (ref "E6") (pin "1") (pinfunction "R_1") (pintype "input"))
      (node (ref "E6") (pin "10") (pinfunction "L_10") (pintype "input"))
      (node (ref "E6") (pin "14") (pinfunction "I3_14") (pintype "input"))
      (node (ref "E6") (pin "15") (pinfunction "I2_15") (pintype "input"))
      (node (ref "E6") (pin "2") (pinfunction "I1_2") (pintype "input"))
      (node (ref "E6") (pin "3") (pinfunction "I0_3") (pintype "input"))
      (node (ref "E7") (pin "1") (pinfunction "CLR_1") (pintype "input"))
      (node (ref "E7") (pin "13") (pinfunction "CLR_13") (pintype "input"))
      (node (ref "E8") (pin "10") (pinfunction "PRE_10") (pintype "input"))
      (node (ref "E8") (pin "4") (pinfunction "PRE_4") (pintype "input"))
      (node (ref "IC1") (pin "1") (pinfunction "I0_1") (pintype "input"))
      (node (ref "IC1") (pin "2") (pinfunction "I1_2") (pintype "input"))
      (node (ref "IC2") (pin "1") (pinfunction "I0_1") (pintype "input"))
      (node (ref "IC2") (pin "2") (pinfunction "I1_2") (pintype "input"))
      (node (ref "N14") (pin "A2") (pinfunction "1_A2") (pintype "bidirectional"))
      (node (ref "N15") (pin "A2") (pinfunction "1_A2") (pintype "bidirectional"))
      (node (ref "N16") (pin "A2") (pinfunction "1_A2") (pintype "bidirectional"))
      (node (ref "OSC") (pin "8") (pinfunction "VCC_8") (pintype "power_in"))
      (node (ref "OSC2") (pin "14") (pinfunction "VCC_14") (pintype "power_in"))
      (node (ref "Q3") (pin "1") (pinfunction "E_1") (pintype "passive"))
      (node (ref "R14") (pin "2") (pinfunction "2_2") (pintype "passive"))
      (node (ref "R15") (pin "2") (pinfunction "2_2") (pintype "passive"))
      (node (ref "R16") (pin "2") (pinfunction "2_2") (pintype "passive"))
      (node (ref "R21") (pin "2") (pinfunction "2_2") (pintype "passive"))
      (node (ref "R24") (pin "2") (pinfunction "2_2") (pintype "passive"))
      (node (ref "R8") (pin "2") (pinfunction "2_2") (pintype "passive"))
    )
    (net (code "165") (name "X8_RATE") (class "Default")
      (node (ref "BAUD") (pin "10") (pinfunction "10_10") (pintype "passive"))
      (node (ref "BAUD") (pin "12") (pinfunction "12_12") (pintype "passive"))
      (node (ref "BAUD") (pin "14") (pinfunction "14_14") (pintype "passive"))
      (node (ref "BAUD") (pin "16") (pinfunction "16_16") (pintype "passive"))
      (node (ref "BAUD") (pin "18") (pinfunction "18_18") (pintype "passive"))
      (node (ref "BAUD") (pin "2") (pinfunction "2_2") (pintype "passive"))
      (node (ref "BAUD") (pin "20") (pinfunction "20_20") (pintype "passive"))
      (node (ref "BAUD") (pin "22") (pinfunction "22_22") (pintype "passive"))
      (node (ref "BAUD") (pin "24") (pinfunction "24_24") (pintype "passive"))
      (node (ref "BAUD") (pin "26") (pinfunction "26_26") (pintype "passive"))
      (node (ref "BAUD") (pin "4") (pinfunction "4_4") (pintype "passive"))
      (node (ref "BAUD") (pin "6") (pinfunction "6_6") (pintype "passive"))
      (node (ref "BAUD") (pin "8") (pinfunction "8_8") (pintype "passive"))
    )
    (net (code "166") (name "unconnected-(E3B-Q-Pad9)") (class "Default")
      (node (ref "E3") (pin "9") (pinfunction "Q_9") (pintype "output"))
    )
    (net (code "167") (name "unconnected-(E4A-Q-Pad5)") (class "Default")
      (node (ref "E4") (pin "5") (pinfunction "Q_5") (pintype "output"))
    )
    (net (code "168") (name "unconnected-(E4B-Q-Pad9)") (class "Default")
      (node (ref "E4") (pin "9") (pinfunction "Q_9") (pintype "output"))
    )
    (net (code "169") (name "unconnected-(E6A-Q4-Pad12)") (class "Default")
      (node (ref "E6") (pin "12") (pinfunction "Q4_12") (pintype "output"))
    )
    (net (code "170") (name "unconnected-(E7B-~{Q}-Pad8)") (class "Default")
      (node (ref "E7") (pin "8") (pinfunction "~{Q}_8") (pintype "output"))
    )
    (net (code "171") (name "unconnected-(E14A-QA-Pad12)") (class "Default")
      (node (ref "E14") (pin "12") (pinfunction "QA_12") (pintype "output"))
    )
    (net (code "172") (name "unconnected-(E14A-QB-Pad9)") (class "Default")
      (node (ref "E14") (pin "9") (pinfunction "QB_9") (pintype "output"))
    )
    (net (code "173") (name "unconnected-(E14A-QC-Pad8)") (class "Default")
      (node (ref "E14") (pin "8") (pinfunction "QC_8") (pintype "output"))
    )
    (net (code "174") (name "unconnected-(E16B-Q-Pad9)") (class "Default")
      (node (ref "E16") (pin "9") (pinfunction "Q_9") (pintype "output"))
    )
    (net (code "175") (name "unconnected-(E20B-Q-Pad9)") (class "Default")
      (node (ref "E20") (pin "9") (pinfunction "Q_9") (pintype "output"))
    )
    (net (code "176") (name "unconnected-(E25A-I5-Pad12)") (class "Default")
      (node (ref "E25") (pin "12") (pinfunction "I5_12") (pintype "passive"))
    )
    (net (code "177") (name "unconnected-(E25A-I6-Pad11)") (class "Default")
      (node (ref "E25") (pin "11") (pinfunction "I6_11") (pintype "passive"))
    )
    (net (code "178") (name "unconnected-(E26A-Q1-Pad7)") (class "Default")
      (node (ref "E26") (pin "7") (pinfunction "Q1_7") (pintype "output"))
    )
    (net (code "179") (name "unconnected-(E26A-Q3-Pad11)") (class "Default")
      (node (ref "E26") (pin "11") (pinfunction "Q3_11") (pintype "output"))
    )
    (net (code "180") (name "unconnected-(E26A-Q4-Pad12)") (class "Default")
      (node (ref "E26") (pin "12") (pinfunction "Q4_12") (pintype "output"))
    )
    (net (code "181") (name "unconnected-(E28A-Q4-Pad12)") (class "Default")
      (node (ref "E28") (pin "12") (pinfunction "Q4_12") (pintype "output"))
    )
    (net (code "182") (name "unconnected-(E29A-Q-Pad5)") (class "Default")
      (node (ref "E29") (pin "5") (pinfunction "Q_5") (pintype "output"))
    )
    (net (code "183") (name "unconnected-(E29B-~{Q}-Pad8)") (class "Default")
      (node (ref "E29") (pin "8") (pinfunction "~{Q}_8") (pintype "output"))
    )
    (net (code "184") (name "unconnected-(E31A-Q4-Pad12)") (class "Default")
      (node (ref "E31") (pin "12") (pinfunction "Q4_12") (pintype "output"))
    )
    (net (code "185") (name "unconnected-(E39A-I5-Pad12)") (class "Default")
      (node (ref "E39") (pin "12") (pinfunction "I5_12") (pintype "passive"))
    )
    (net (code "186") (name "unconnected-(E39A-I6-Pad11)") (class "Default")
      (node (ref "E39") (pin "11") (pinfunction "I6_11") (pintype "passive"))
    )
    (net (code "187") (name "unconnected-(E48B-~{Q}-Pad8)") (class "Default")
      (node (ref "E48") (pin "8") (pinfunction "~{Q}_8") (pintype "output"))
    )
    (net (code "188") (name "unconnected-(IC3A-QD-Pad6)") (class "Default")
      (node (ref "IC3") (pin "6") (pinfunction "QD_6") (pintype "output"))
    )
    (net (code "189") (name "unconnected-(IC5A-QC-Pad5)") (class "Default")
      (node (ref "IC5") (pin "5") (pinfunction "QC_5") (pintype "output"))
    )
    (net (code "190") (name "unconnected-(J1-4-PadD)") (class "Default")
      (node (ref "J1") (pin "D") (pinfunction "4_D") (pintype "bidirectional"))
    )
    (net (code "191") (name "unconnected-(J1-10-PadL)") (class "Default")
      (node (ref "J1") (pin "L") (pinfunction "10_L") (pintype "bidirectional"))
    )
    (net (code "192") (name "unconnected-(J1-12-PadN)") (class "Default")
      (node (ref "J1") (pin "N") (pinfunction "12_N") (pintype "bidirectional"))
    )
    (net (code "193") (name "unconnected-(J1-13-PadP)") (class "Default")
      (node (ref "J1") (pin "P") (pinfunction "13_P") (pintype "bidirectional"))
    )
    (net (code "194") (name "unconnected-(J1-14-PadR)") (class "Default")
      (node (ref "J1") (pin "R") (pinfunction "14_R") (pintype "bidirectional"))
    )
    (net (code "195") (name "unconnected-(J1-16-PadT)") (class "Default")
      (node (ref "J1") (pin "T") (pinfunction "16_T") (pintype "bidirectional"))
    )
    (net (code "196") (name "unconnected-(J1-17-PadU)") (class "Default")
      (node (ref "J1") (pin "U") (pinfunction "17_U") (pintype "bidirectional"))
    )
    (net (code "197") (name "unconnected-(J1-19-PadW)") (class "Default")
      (node (ref "J1") (pin "W") (pinfunction "19_W") (pintype "bidirectional"))
    )
    (net (code "198") (name "unconnected-(J1-20-PadX)") (class "Default")
      (node (ref "J1") (pin "X") (pinfunction "20_X") (pintype "bidirectional"))
    )
    (net (code "199") (name "unconnected-(J1-21-PadY)") (class "Default")
      (node (ref "J1") (pin "Y") (pinfunction "21_Y") (pintype "bidirectional"))
    )
    (net (code "200") (name "unconnected-(J1-22-PadZ)") (class "Default")
      (node (ref "J1") (pin "Z") (pinfunction "22_Z") (pintype "bidirectional"))
    )
    (net (code "201") (name "unconnected-(J1-24-PadBB)") (class "Default")
      (node (ref "J1") (pin "BB") (pinfunction "24_BB") (pintype "bidirectional"))
    )
    (net (code "202") (name "unconnected-(J1-25-PadCC)") (class "Default")
      (node (ref "J1") (pin "CC") (pinfunction "25_CC") (pintype "bidirectional"))
    )
    (net (code "203") (name "unconnected-(J1-28-PadFF)") (class "Default")
      (node (ref "J1") (pin "FF") (pinfunction "28_FF") (pintype "bidirectional"))
    )
    (net (code "204") (name "unconnected-(J1-29-PadHH)") (class "Default")
      (node (ref "J1") (pin "HH") (pinfunction "29_HH") (pintype "bidirectional"))
    )
    (net (code "205") (name "unconnected-(J1-30-PadJJ)") (class "Default")
      (node (ref "J1") (pin "JJ") (pinfunction "30_JJ") (pintype "bidirectional"))
    )
    (net (code "206") (name "unconnected-(J1-32-PadLL)") (class "Default")
      (node (ref "J1") (pin "LL") (pinfunction "32_LL") (pintype "bidirectional"))
    )
    (net (code "207") (name "unconnected-(J1-33-PadMM)") (class "Default")
      (node (ref "J1") (pin "MM") (pinfunction "33_MM") (pintype "bidirectional"))
    )
    (net (code "208") (name "unconnected-(J1-34-PadNN)") (class "Default")
      (node (ref "J1") (pin "NN") (pinfunction "34_NN") (pintype "bidirectional"))
    )
    (net (code "209") (name "unconnected-(J1-36-PadRR)") (class "Default")
      (node (ref "J1") (pin "RR") (pinfunction "36_RR") (pintype "bidirectional"))
    )
    (net (code "210") (name "unconnected-(J1-37-PadSS)") (class "Default")
      (node (ref "J1") (pin "SS") (pinfunction "37_SS") (pintype "bidirectional"))
    )
    (net (code "211") (name "unconnected-(J1-38-PadTT)") (class "Default")
      (node (ref "J1") (pin "TT") (pinfunction "38_TT") (pintype "bidirectional"))
    )
    (net (code "212") (name "~{ACCLR}") (class "Default")
      (node (ref "E27") (pin "4") (pinfunction "O_4") (pintype "open_collector"))
      (node (ref "N16") (pin "P2") (pinfunction "1_P2") (pintype "bidirectional"))
    )
    (net (code "213") (name "~{BMB3}") (class "Default")
      (node (ref "N15") (pin "H1") (pinfunction "1_H1") (pintype "bidirectional"))
      (node (ref "RX3") (pin "1") (pinfunction "1_1") (pintype "passive"))
      (node (ref "TX3") (pin "1") (pinfunction "1_1") (pintype "passive"))
    )
    (net (code "214") (name "~{BMB4}") (class "Default")
      (node (ref "N15") (pin "L1") (pinfunction "1_L1") (pintype "bidirectional"))
      (node (ref "RX4") (pin "1") (pinfunction "1_1") (pintype "passive"))
      (node (ref "TX4") (pin "1") (pinfunction "1_1") (pintype "passive"))
    )
    (net (code "215") (name "~{BMB5}") (class "Default")
      (node (ref "N15") (pin "P1") (pinfunction "1_P1") (pintype "bidirectional"))
      (node (ref "RX5") (pin "1") (pinfunction "1_1") (pintype "passive"))
      (node (ref "TX5") (pin "1") (pinfunction "1_1") (pintype "passive"))
    )
    (net (code "216") (name "~{BMB6}") (class "Default")
      (node (ref "N15") (pin "D2") (pinfunction "1_D2") (pintype "bidirectional"))
      (node (ref "RX6") (pin "1") (pinfunction "1_1") (pintype "passive"))
      (node (ref "TX6") (pin "1") (pinfunction "1_1") (pintype "passive"))
    )
    (net (code "217") (name "~{BMB7}") (class "Default")
      (node (ref "N15") (pin "H2") (pinfunction "1_H2") (pintype "bidirectional"))
      (node (ref "RX7") (pin "1") (pinfunction "1_1") (pintype "passive"))
      (node (ref "TX7") (pin "1") (pinfunction "1_1") (pintype "passive"))
    )
    (net (code "218") (name "~{BMB8}") (class "Default")
      (node (ref "N15") (pin "M2") (pinfunction "1_M2") (pintype "bidirectional"))
      (node (ref "RX8") (pin "1") (pinfunction "1_1") (pintype "passive"))
      (node (ref "TX8") (pin "1") (pinfunction "1_1") (pintype "passive"))
    )
    (net (code "219") (name "~{INIT}") (class "Default")
      (node (ref "E13") (pin "4") (pinfunction "PRE_4") (pintype "input"))
      (node (ref "E16") (pin "13") (pinfunction "CLR_13") (pintype "input"))
      (node (ref "E19") (pin "13") (pinfunction "I2_13") (pintype "input"))
      (node (ref "E19") (pin "2") (pinfunction "I1_2") (pintype "input"))
      (node (ref "E20") (pin "4") (pinfunction "PRE_4") (pintype "input"))
      (node (ref "E23") (pin "13") (pinfunction "I1_13") (pintype "input"))
      (node (ref "E28") (pin "1") (pinfunction "R_1") (pintype "input"))
      (node (ref "E29") (pin "13") (pinfunction "CLR_13") (pintype "input"))
      (node (ref "E31") (pin "1") (pinfunction "R_1") (pintype "input"))
      (node (ref "E42") (pin "2") (pinfunction "O_2") (pintype "output"))
      (node (ref "E48") (pin "10") (pinfunction "PRE_10") (pintype "input"))
      (node (ref "SV1") (pin "3") (pinfunction "3_3") (pintype "passive"))
      (node (ref "SV2") (pin "3") (pinfunction "3_3") (pintype "passive"))
      (node (ref "SV3") (pin "3") (pinfunction "3_3") (pintype "passive"))
    )
    (net (code "220") (name "~{IOB0}") (class "Default")
      (node (ref "N16") (pin "B1") (pinfunction "1_B1") (pintype "bidirectional"))
    )
    (net (code "221") (name "~{IOB1}") (class "Default")
      (node (ref "N16") (pin "D1") (pinfunction "1_D1") (pintype "bidirectional"))
    )
    (net (code "222") (name "~{IOB2}") (class "Default")
      (node (ref "N16") (pin "E1") (pinfunction "1_E1") (pintype "bidirectional"))
    )
    (net (code "223") (name "~{IOB3}") (class "Default")
      (node (ref "N16") (pin "H1") (pinfunction "1_H1") (pintype "bidirectional"))
    )
    (net (code "224") (name "~{IOB4}") (class "Default")
      (node (ref "E2") (pin "13") (pinfunction "O_13") (pintype "open_collector"))
      (node (ref "N16") (pin "J1") (pinfunction "1_J1") (pintype "bidirectional"))
    )
    (net (code "225") (name "~{IOB5}") (class "Default")
      (node (ref "E2") (pin "10") (pinfunction "O_10") (pintype "open_collector"))
      (node (ref "N16") (pin "L1") (pinfunction "1_L1") (pintype "bidirectional"))
    )
    (net (code "226") (name "~{IOB6}") (class "Default")
      (node (ref "E2") (pin "4") (pinfunction "O_4") (pintype "open_collector"))
      (node (ref "N16") (pin "M1") (pinfunction "1_M1") (pintype "bidirectional"))
    )
    (net (code "227") (name "~{IOB7}") (class "Default")
      (node (ref "E2") (pin "1") (pinfunction "O_1") (pintype "open_collector"))
      (node (ref "N16") (pin "P1") (pinfunction "1_P1") (pintype "bidirectional"))
    )
    (net (code "228") (name "~{IOB8}") (class "Default")
      (node (ref "E15") (pin "13") (pinfunction "O_13") (pintype "open_collector"))
      (node (ref "N16") (pin "S1") (pinfunction "1_S1") (pintype "bidirectional"))
    )
    (net (code "229") (name "~{IOB9}") (class "Default")
      (node (ref "E15") (pin "10") (pinfunction "O_10") (pintype "open_collector"))
      (node (ref "N16") (pin "D2") (pinfunction "1_D2") (pintype "bidirectional"))
    )
    (net (code "230") (name "~{IOB10}") (class "Default")
      (node (ref "E15") (pin "4") (pinfunction "O_4") (pintype "open_collector"))
      (node (ref "N16") (pin "E2") (pinfunction "1_E2") (pintype "bidirectional"))
    )
    (net (code "231") (name "~{IOB11}") (class "Default")
      (node (ref "E15") (pin "1") (pinfunction "O_1") (pintype "open_collector"))
      (node (ref "N16") (pin "H2") (pinfunction "1_H2") (pintype "bidirectional"))
    )
    (net (code "232") (name "~{IRQ}") (class "Default")
      (node (ref "E27") (pin "10") (pinfunction "O_10") (pintype "open_collector"))
      (node (ref "E33") (pin "1") (pinfunction "O_1") (pintype "open_collector"))
      (node (ref "N16") (pin "M2") (pinfunction "1_M2") (pintype "bidirectional"))
      (node (ref "SV1") (pin "4") (pinfunction "4_4") (pintype "passive"))
      (node (ref "SV2") (pin "4") (pinfunction "4_4") (pintype "passive"))
      (node (ref "SV3") (pin "4") (pinfunction "4_4") (pintype "passive"))
    )
    (net (code "233") (name "~{KCC}") (class "Default")
      (node (ref "E23") (pin "12") (pinfunction "I0_12") (pintype "input"))
      (node (ref "E23") (pin "6") (pinfunction "O_6") (pintype "output"))
      (node (ref "E48") (pin "13") (pinfunction "CLR_13") (pintype "input"))
      (node (ref "E9") (pin "3") (pinfunction "I_3") (pintype "input"))
    )
    (net (code "234") (name "~{KRS}") (class "Default")
      (node (ref "E23") (pin "8") (pinfunction "O_8") (pintype "output"))
      (node (ref "E9") (pin "5") (pinfunction "I_5") (pintype "input"))
    )
    (net (code "235") (name "~{KSF}") (class "Default")
      (node (ref "E11") (pin "11") (pinfunction "I0_11") (pintype "input"))
      (node (ref "E23") (pin "3") (pinfunction "O_3") (pintype "output"))
    )
    (net (code "236") (name "~{LAST_UNIT}") (class "Default")
      (node (ref "E12") (pin "12") (pinfunction "I0_12") (pintype "input"))
      (node (ref "E8") (pin "6") (pinfunction "~{Q}_6") (pintype "output"))
    )
    (net (code "237") (name "~{LINE}") (class "Default")
      (node (ref "E29") (pin "6") (pinfunction "~{Q}_6") (pintype "output"))
      (node (ref "E9") (pin "9") (pinfunction "I_9") (pintype "input"))
      (node (ref "R13") (pin "1") (pinfunction "1_1") (pintype "passive"))
      (node (ref "R14") (pin "1") (pinfunction "1_1") (pintype "passive"))
      (node (ref "SV1") (pin "10") (pinfunction "10_10") (pintype "passive"))
      (node (ref "SV2") (pin "10") (pinfunction "10_10") (pintype "passive"))
      (node (ref "SV3") (pin "10") (pinfunction "10_10") (pintype "passive"))
    )
    (net (code "238") (name "~{P_PULSE}") (class "Default")
      (node (ref "E10") (pin "13") (pinfunction "S_13") (pintype "input"))
      (node (ref "E11") (pin "8") (pinfunction "I0_8") (pintype "input"))
      (node (ref "E6") (pin "13") (pinfunction "S_13") (pintype "input"))
      (node (ref "E7") (pin "9") (pinfunction "Q_9") (pintype "output"))
    )
    (net (code "239") (name "~{RFLG}") (class "Default")
      (node (ref "E11") (pin "12") (pinfunction "I1_12") (pintype "input"))
      (node (ref "E48") (pin "6") (pinfunction "~{Q}_6") (pintype "output"))
    )
    (net (code "240") (name "~{RX_ACTIVE8}") (class "Default")
      (node (ref "E12") (pin "3") (pinfunction "O_3") (pintype "output"))
      (node (ref "E16") (pin "11") (pinfunction "CLK_11") (pintype "input"))
      (node (ref "E21") (pin "3") (pinfunction "I_3") (pintype "input"))
      (node (ref "E39") (pin "1") (pinfunction "I4_1") (pintype "input"))
    )
    (net (code "241") (name "~{RX_ACTIVE}") (class "Default")
      (node (ref "E12") (pin "13") (pinfunction "I1_13") (pintype "input"))
      (node (ref "E12") (pin "4") (pinfunction "I0_4") (pintype "input"))
      (node (ref "E7") (pin "6") (pinfunction "~{Q}_6") (pintype "output"))
    )
    (net (code "242") (name "~{RX_AGAIN}") (class "Default")
      (node (ref "E16") (pin "10") (pinfunction "PRE_10") (pintype "input"))
      (node (ref "E5") (pin "12") (pinfunction "O_12") (pintype "output"))
      (node (ref "E7") (pin "4") (pinfunction "PRE_4") (pintype "input"))
    )
    (net (code "243") (name "~{RX_DIV2}") (class "Default")
      (node (ref "E11") (pin "9") (pinfunction "I1_9") (pintype "input"))
      (node (ref "E4") (pin "11") (pinfunction "CLK_11") (pintype "input"))
      (node (ref "E4") (pin "2") (pinfunction "D_2") (pintype "input"))
      (node (ref "E4") (pin "6") (pinfunction "~{Q}_6") (pintype "output"))
    )
    (net (code "244") (name "~{RX_DIV4}") (class "Default")
      (node (ref "E4") (pin "12") (pinfunction "D_12") (pintype "input"))
      (node (ref "E4") (pin "8") (pinfunction "~{Q}_8") (pintype "output"))
      (node (ref "E7") (pin "10") (pinfunction "PRE_10") (pintype "input"))
      (node (ref "E8") (pin "11") (pinfunction "CLK_11") (pintype "input"))
    )
    (net (code "245") (name "~{RX_DIV}") (class "Default")
      (node (ref "E3") (pin "6") (pinfunction "~{Q}_6") (pintype "output"))
      (node (ref "E4") (pin "3") (pinfunction "CLK_3") (pintype "input"))
    )
    (net (code "246") (name "~{R_DONE}") (class "Default")
      (node (ref "E12") (pin "10") (pinfunction "I1_10") (pintype "input"))
      (node (ref "E12") (pin "11") (pinfunction "O_11") (pintype "output"))
      (node (ref "E21") (pin "11") (pinfunction "I_11") (pintype "input"))
      (node (ref "E36") (pin "4") (pinfunction "I0_4") (pintype "input"))
      (node (ref "E36") (pin "5") (pinfunction "I1_5") (pintype "input"))
      (node (ref "R15") (pin "1") (pinfunction "1_1") (pintype "passive"))
    )
    (net (code "247") (name "~{R_RUN}") (class "Default")
      (node (ref "E32") (pin "10") (pinfunction "I1_10") (pintype "input"))
      (node (ref "E32") (pin "9") (pinfunction "I0_9") (pintype "input"))
      (node (ref "E48") (pin "9") (pinfunction "Q_9") (pintype "output"))
      (node (ref "Q2") (pin "2") (pinfunction "B_2") (pintype "passive"))
    )
    (net (code "248") (name "~{SKIP}") (class "Default")
      (node (ref "E27") (pin "1") (pinfunction "O_1") (pintype "open_collector"))
      (node (ref "E27") (pin "13") (pinfunction "O_13") (pintype "open_collector"))
      (node (ref "N16") (pin "K2") (pinfunction "1_K2") (pintype "bidirectional"))
      (node (ref "SV1") (pin "6") (pinfunction "6_6") (pintype "passive"))
      (node (ref "SV2") (pin "6") (pinfunction "6_6") (pintype "passive"))
      (node (ref "SV3") (pin "6") (pinfunction "6_6") (pintype "passive"))
    )
    (net (code "249") (name "~{SPIKE_DET}") (class "Default")
      (node (ref "E11") (pin "2") (pinfunction "I0_2") (pintype "input"))
      (node (ref "E16") (pin "8") (pinfunction "~{Q}_8") (pintype "output"))
    )
    (net (code "250") (name "~{START}") (class "Default")
      (node (ref "E20") (pin "8") (pinfunction "~{Q}_8") (pintype "output"))
      (node (ref "E29") (pin "1") (pinfunction "CLR_1") (pintype "input"))
    )
    (net (code "251") (name "~{TCF}") (class "Default")
      (node (ref "E19") (pin "1") (pinfunction "I0_1") (pintype "input"))
      (node (ref "E40") (pin "6") (pinfunction "O_6") (pintype "output"))
    )
    (net (code "252") (name "~{TFLG}") (class "Default")
      (node (ref "E13") (pin "9") (pinfunction "Q_9") (pintype "output"))
      (node (ref "E45") (pin "11") (pinfunction "I0_11") (pintype "input"))
    )
    (net (code "253") (name "~{TPC}") (class "Default")
      (node (ref "E28") (pin "13") (pinfunction "S_13") (pintype "input"))
      (node (ref "E31") (pin "13") (pinfunction "S_13") (pintype "input"))
      (node (ref "E40") (pin "8") (pinfunction "O_8") (pintype "output"))
      (node (ref "E42") (pin "11") (pinfunction "I_11") (pintype "input"))
    )
    (net (code "254") (name "~{TSF}") (class "Default")
      (node (ref "E40") (pin "3") (pinfunction "O_3") (pintype "output"))
      (node (ref "E45") (pin "12") (pinfunction "I1_12") (pintype "input"))
    )
    (net (code "255") (name "~{TX_ACTIVE}") (class "Default")
      (node (ref "E20") (pin "5") (pinfunction "Q_5") (pintype "output"))
      (node (ref "E26") (pin "4") (pinfunction "D_4") (pintype "input"))
    )
    (net (code "256") (name "~{TX_DIV}") (class "Default")
      (node (ref "DL1") (pin "1") (pinfunction "1_1") (pintype "passive"))
      (node (ref "E13") (pin "6") (pinfunction "~{Q}_6") (pintype "output"))
      (node (ref "E19") (pin "4") (pinfunction "I1_4") (pintype "input"))
      (node (ref "R21") (pin "1") (pinfunction "1_1") (pintype "passive"))
    )
    (net (code "257") (name "~{TX_SHIFT}") (class "Default")
      (node (ref "E25") (pin "6") (pinfunction "O_6") (pintype "output"))
      (node (ref "E28") (pin "6") (pinfunction "C_6") (pintype "input"))
      (node (ref "E31") (pin "6") (pinfunction "C_6") (pintype "input"))
      (node (ref "E42") (pin "3") (pinfunction "I_3") (pintype "input"))
    )
  )
)
